# 94330_SKYPULSE_IOC_V1_2.net
KiCad netlist of a schematic drawn in Altium Designer
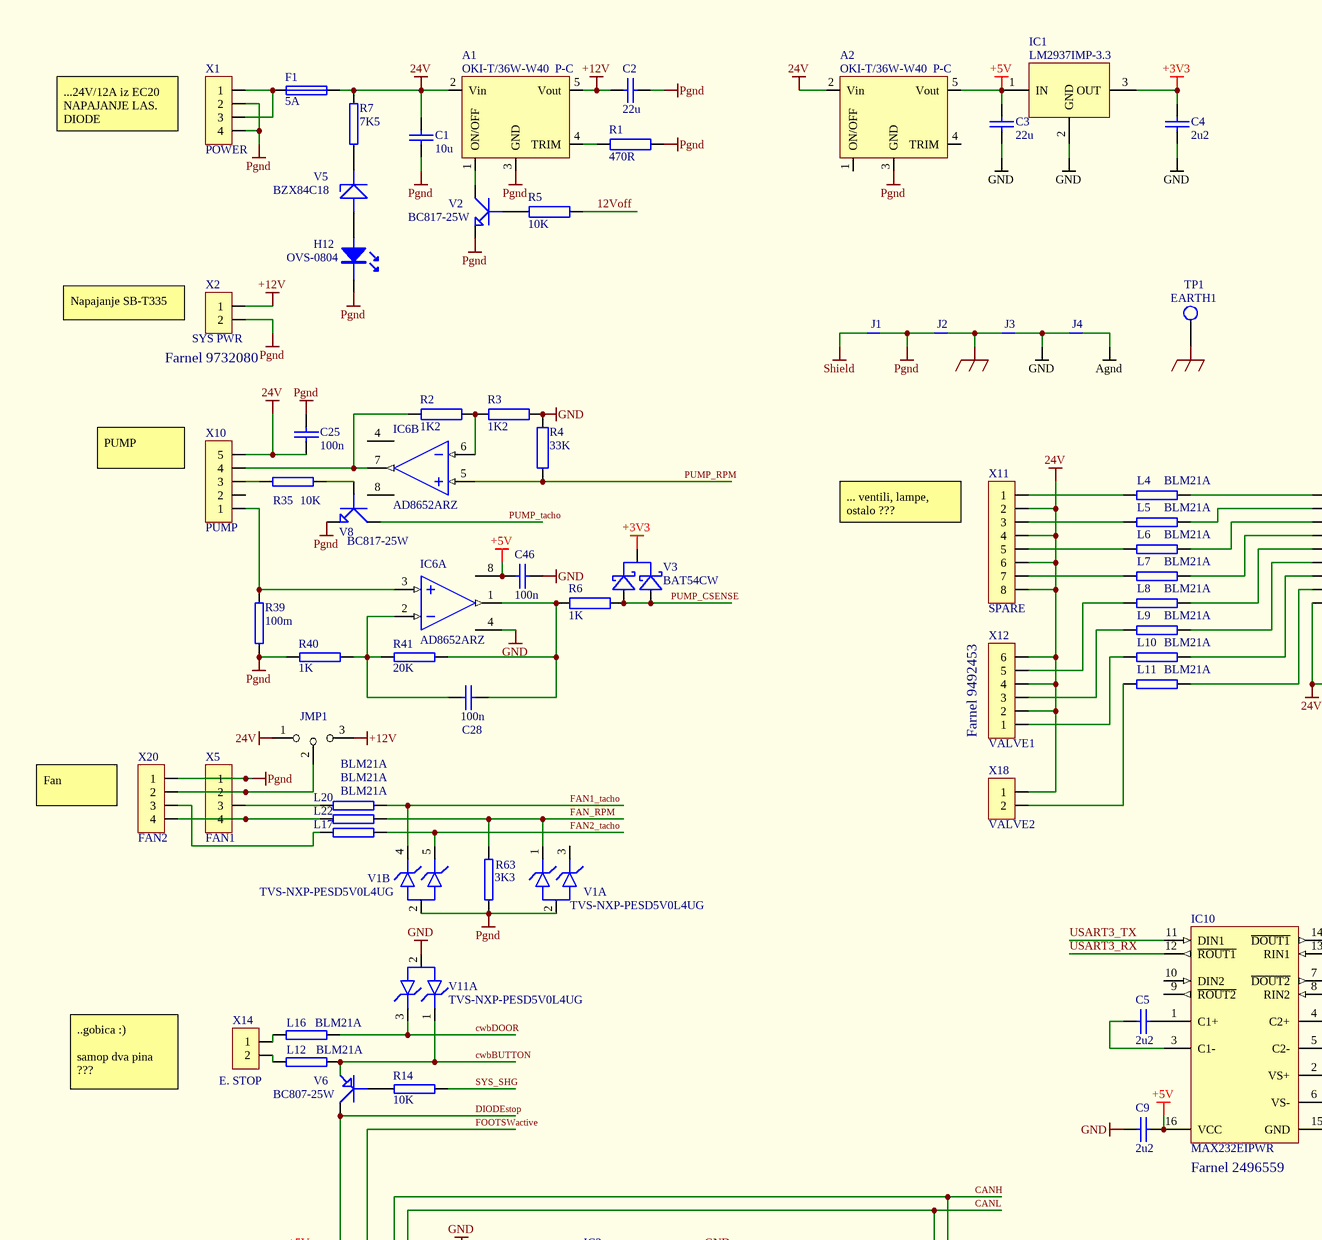
[diagram p0: 94330_SKYPULSE IOC_V1.2.SchDoc, top left]
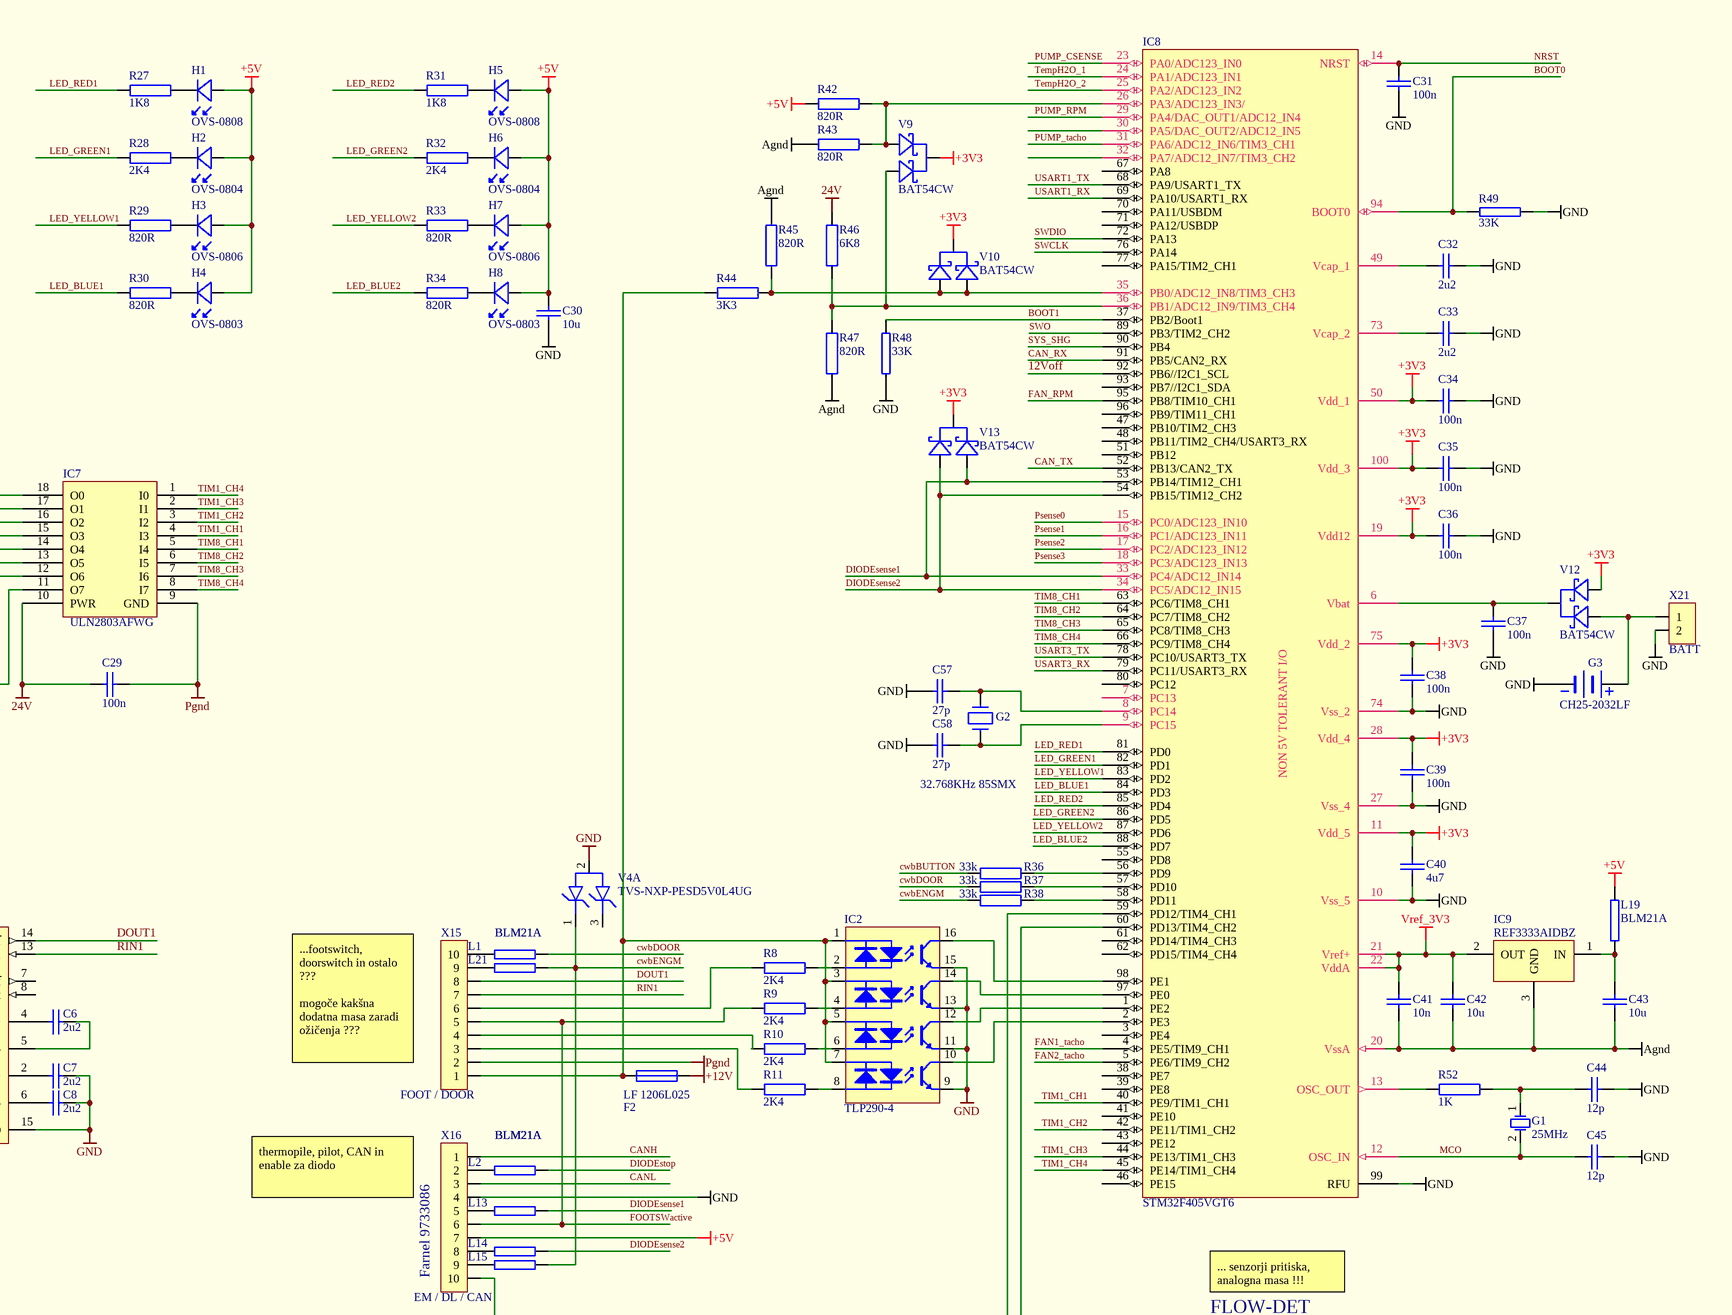
[diagram p1: 94330_SKYPULSE IOC_V1.2.SchDoc, top right]
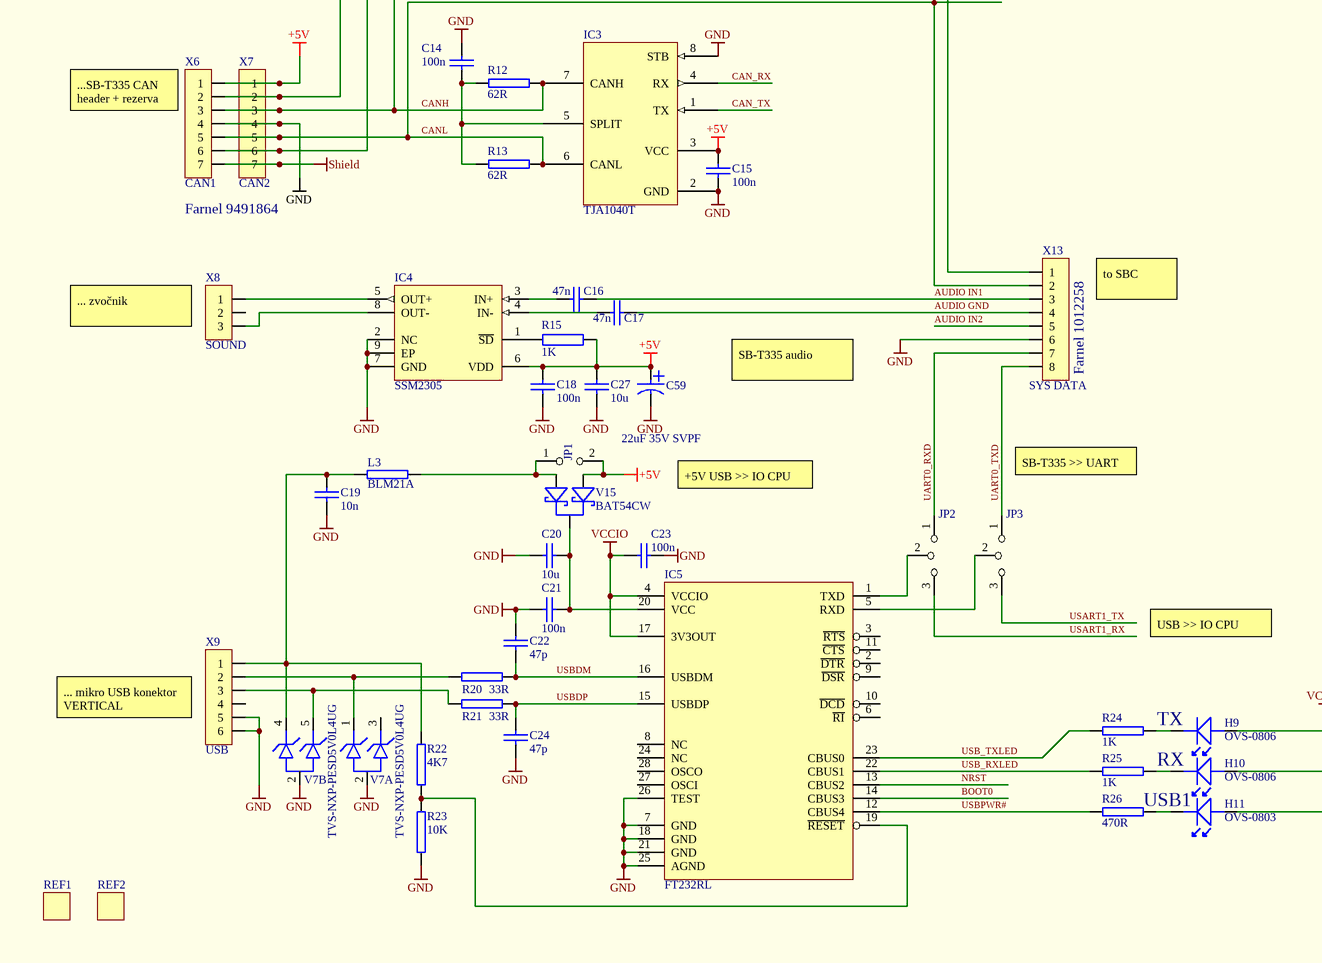
[diagram p2: 94330_SKYPULSE IOC_V1.2.SchDoc, bottom left]
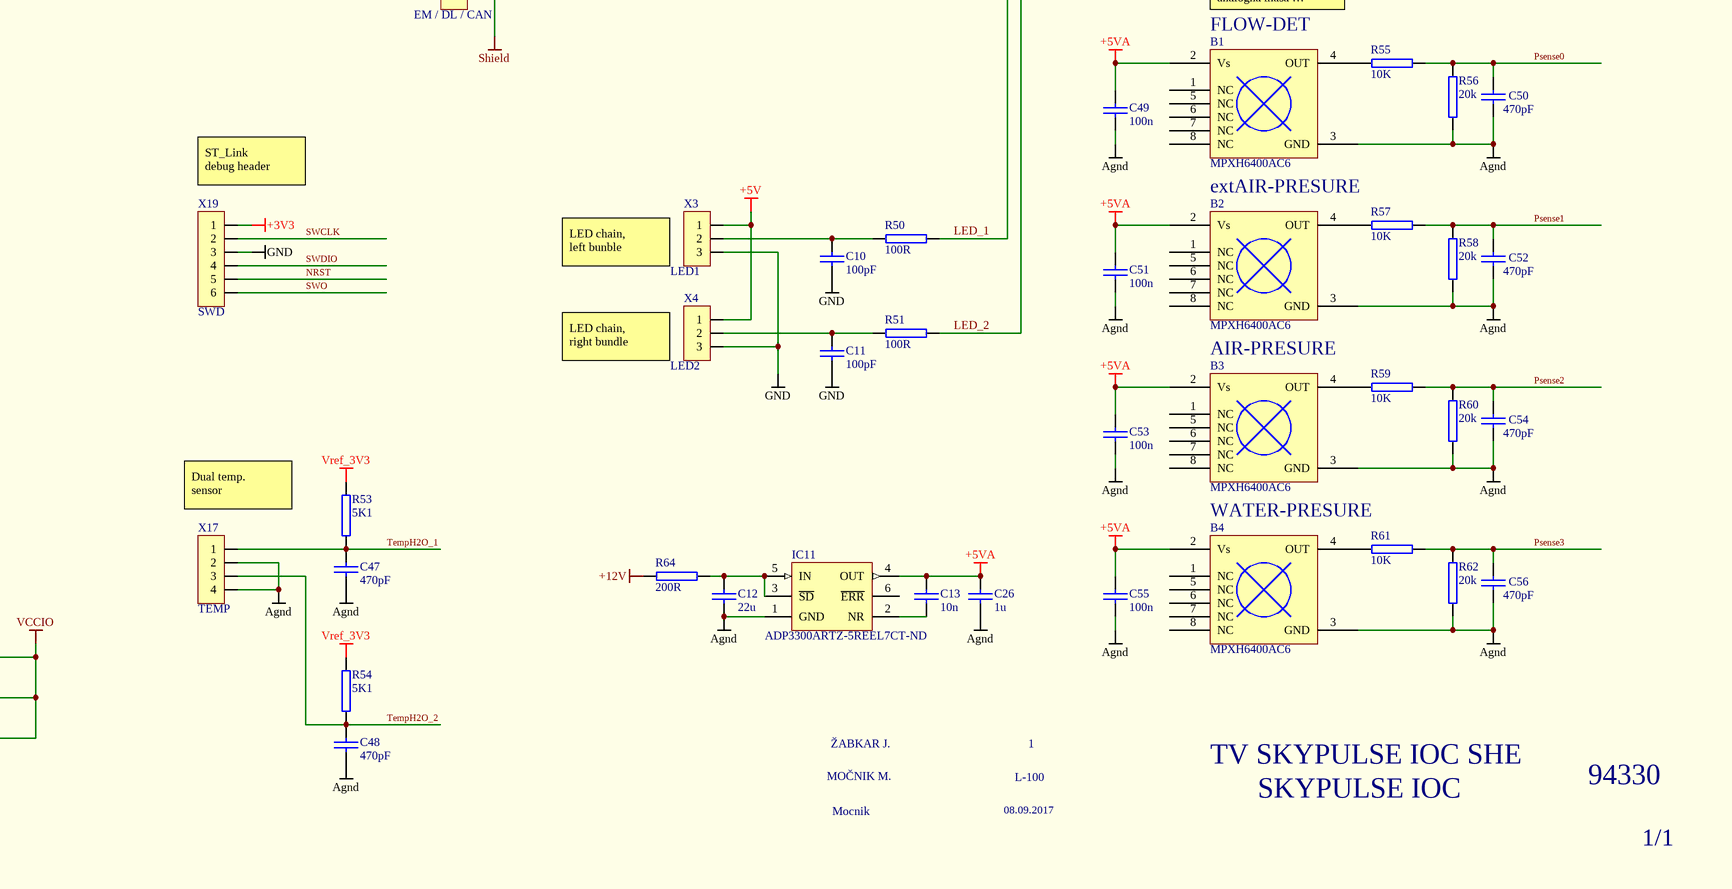
[diagram p3: 94330_SKYPULSE IOC_V1.2.SchDoc, bottom right]

(export (version "E")
  (design (tool "Eeschema 10.0.6"))
  (components
    (comp (ref "A1")
      (value "OKI-T/36W-W40  P-C")
      (footprint "DC-DC_OKI-T/36W-W40")
      (libsource (lib "Mlk-sch") (part "MURATA_OKI-T/36W-W40  X-C"))
    )
    (comp (ref "A2")
      (value "OKI-T/36W-W40  P-C")
      (footprint "DC-DC_OKI-T/36W-W40")
      (libsource (lib "Mlk-sch") (part "MURATA_OKI-T/36W-W40  X-C"))
    )
    (comp (ref "B1")
      (value "MPXH6400AC6")
      (footprint "SOIC127P1030-8N_MPXH6400AC6")
      (description "MPXH6400A Pressure sensor, 400kPa")
      (libsource (lib "*") (part "MPXH6400A"))
    )
    (comp (ref "B2")
      (value "MPXH6400AC6")
      (footprint "SOIC127P1030-8N_MPXH6400AC6")
      (description "MPXH6400A Pressure sensor, 400kPa")
      (libsource (lib "*") (part "MPXH6400A"))
    )
    (comp (ref "B3")
      (value "MPXH6400AC6")
      (footprint "SOIC127P1030-8N_MPXH6400AC6")
      (description "MPXH6400A Pressure sensor, 400kPa")
      (libsource (lib "*") (part "MPXH6400A"))
    )
    (comp (ref "B4")
      (value "MPXH6400AC6")
      (footprint "SOIC127P1030-8N_MPXH6400AC6")
      (description "MPXH6400A Pressure sensor, 400kPa")
      (libsource (lib "*") (part "MPXH6400A"))
    )
    (comp (ref "C1")
      (value "10u")
      (footprint "CAPC3225N")
      (description "Capacitor 1210")
      (libsource (lib "altium-import") (part "root_2_Cap_"))
    )
    (comp (ref "C2")
      (value "22u")
      (footprint "CAPC3225N")
      (description "Capacitor 1210")
      (libsource (lib "altium-import") (part "root_1_Cap_"))
    )
    (comp (ref "C3")
      (value "22u")
      (footprint "CAPC3225N")
      (description "Capacitor 1210")
      (libsource (lib "altium-import") (part "root_0_Cap_"))
    )
    (comp (ref "C4")
      (value "2u2")
      (footprint "0805-C-IPC-V")
      (description "Capacitor 0805")
      (libsource (lib "altium-import") (part "root_0_Cap_"))
    )
    (comp (ref "C5")
      (value "2u2")
      (footprint "0805-C-IPC-V")
      (description "Capacitor 0805")
      (libsource (lib "altium-import") (part "root_1_Cap_"))
    )
    (comp (ref "C6")
      (value "2u2")
      (footprint "0805-C-IPC-V")
      (description "Capacitor 0805")
      (libsource (lib "altium-import") (part "root_1_Cap_"))
    )
    (comp (ref "C7")
      (value "2u2")
      (footprint "0805-C-IPC-V")
      (description "Capacitor 0805")
      (libsource (lib "altium-import") (part "root_1_Cap_"))
    )
    (comp (ref "C8")
      (value "2u2")
      (footprint "0805-C-IPC-V")
      (description "Capacitor 0805")
      (libsource (lib "altium-import") (part "root_1_Cap_"))
    )
    (comp (ref "C9")
      (value "2u2")
      (footprint "0805-C-IPC-V")
      (description "Capacitor 0805")
      (libsource (lib "altium-import") (part "root_3_Cap_"))
    )
    (comp (ref "C10")
      (value "100pF")
      (footprint "0805-C-IPC-V")
      (description "Capacitor 0805")
      (libsource (lib "*") (part "C"))
    )
    (comp (ref "C11")
      (value "100pF")
      (footprint "0805-C-IPC-V")
      (description "Capacitor 0805")
      (libsource (lib "*") (part "C"))
    )
    (comp (ref "C12")
      (value "22u")
      (footprint "CAPC3225N")
      (description "Capacitor 1210")
      (libsource (lib "altium-import") (part "root_2_Cap_"))
    )
    (comp (ref "C13")
      (value "10n")
      (footprint "0805-C-IPC-V")
      (description "Capacitor 0805")
      (libsource (lib "Main") (part "C"))
    )
    (comp (ref "C14")
      (value "100n")
      (footprint "0805-C-IPC-V")
      (description "Capacitor 0805")
      (libsource (lib "Main") (part "C"))
    )
    (comp (ref "C15")
      (value "100n")
      (footprint "0805-C-IPC-V")
      (description "Capacitor 0805")
      (libsource (lib "Main") (part "C"))
    )
    (comp (ref "C16")
      (value "47n")
      (footprint "0805-C-IPC-V")
      (description "Capacitor 0805")
      (libsource (lib "Main") (part "C"))
    )
    (comp (ref "C17")
      (value "47n")
      (footprint "0805-C-IPC-V")
      (description "Capacitor 0805")
      (libsource (lib "Main") (part "C"))
    )
    (comp (ref "C18")
      (value "100n")
      (footprint "0805-C-IPC-V")
      (description "Capacitor 0805")
      (libsource (lib "Main") (part "C"))
    )
    (comp (ref "C19")
      (value "10n")
      (footprint "0805-C-IPC-V")
      (description "Capacitor 0805")
      (libsource (lib "*") (part "C"))
    )
    (comp (ref "C20")
      (value "10u")
      (footprint "0805-C-IPC-V")
      (description "Capacitor 0805")
      (libsource (lib "*") (part "CAP"))
    )
    (comp (ref "C21")
      (value "100n")
      (footprint "0805-C-IPC-V")
      (description "Capacitor 0805")
      (libsource (lib "*") (part "C"))
    )
    (comp (ref "C22")
      (value "47p")
      (footprint "0805-C-V")
      (description "Capacitor 0805")
      (libsource (lib "*") (part "C"))
    )
    (comp (ref "C23")
      (value "100n")
      (footprint "0805-C-IPC-V")
      (description "Capacitor 0805")
      (libsource (lib "*") (part "C"))
    )
    (comp (ref "C24")
      (value "47p")
      (footprint "0805-C-V")
      (description "Capacitor 0805")
      (libsource (lib "*") (part "C"))
    )
    (comp (ref "C25")
      (value "100n")
      (footprint "0805-C-IPC-V")
      (description "Capacitor 0805")
      (libsource (lib "*") (part "C"))
    )
    (comp (ref "C26")
      (value "1u")
      (footprint "0805-C-IPC-V")
      (description "Capacitor 0805")
      (libsource (lib "Main") (part "C"))
    )
    (comp (ref "C27")
      (value "10u")
      (footprint "0805-C-IPC-V")
      (description "Capacitor 0805")
      (libsource (lib "altium-import") (part "root_2_Cap_"))
    )
    (comp (ref "C28")
      (value "100n")
      (footprint "0805-C-IPC-V")
      (description "Capacitor 0805")
      (libsource (lib "Fotona") (part "Cap"))
    )
    (comp (ref "C29")
      (value "100n")
      (footprint "0805-C-IPC-V")
      (description "Capacitor 0805")
      (libsource (lib "Main") (part "C"))
    )
    (comp (ref "C30")
      (value "10u")
      (footprint "0805-C-IPC-V")
      (description "Capacitor 0805")
      (libsource (lib "Fotona") (part "Cap"))
    )
    (comp (ref "C31")
      (value "100n")
      (footprint "0805-C-IPC-V")
      (description "Capacitor 0805")
      (libsource (lib "Fotona") (part "Cap"))
    )
    (comp (ref "C32")
      (value "2u2")
      (footprint "0805-C-IPC-V")
      (description "Capacitor 0805")
      (libsource (lib "Fotona") (part "Cap"))
    )
    (comp (ref "C33")
      (value "2u2")
      (footprint "0805-C-IPC-V")
      (description "Capacitor 0805")
      (libsource (lib "Fotona") (part "Cap"))
    )
    (comp (ref "C34")
      (value "100n")
      (footprint "0805-C-IPC-V")
      (description "Capacitor 0805")
      (libsource (lib "Main") (part "C"))
    )
    (comp (ref "C35")
      (value "100n")
      (footprint "0805-C-IPC-V")
      (description "Capacitor 0805")
      (libsource (lib "Main") (part "C"))
    )
    (comp (ref "C36")
      (value "100n")
      (footprint "0805-C-IPC-V")
      (description "Capacitor 0805")
      (libsource (lib "Main") (part "C"))
    )
    (comp (ref "C37")
      (value "100n")
      (footprint "0805-C-IPC-V")
      (description "Capacitor 0805")
      (libsource (lib "Main") (part "C"))
    )
    (comp (ref "C38")
      (value "100n")
      (footprint "0805-C-IPC-V")
      (description "Capacitor 0805")
      (libsource (lib "Main") (part "C"))
    )
    (comp (ref "C39")
      (value "100n")
      (footprint "0805-C-IPC-V")
      (description "Capacitor 0805")
      (libsource (lib "Main") (part "C"))
    )
    (comp (ref "C40")
      (value "4u7")
      (footprint "0805-C-IPC-V")
      (description "Capacitor 0805")
      (libsource (lib "Fotona") (part "Cap"))
    )
    (comp (ref "C41")
      (value "10n")
      (footprint "0805-C-IPC-V")
      (description "Capacitor 0805")
      (libsource (lib "Fotona") (part "Cap"))
    )
    (comp (ref "C42")
      (value "10u")
      (footprint "0805-C-IPC-V")
      (description "Capacitor 0805")
      (libsource (lib "Fotona") (part "Cap"))
    )
    (comp (ref "C43")
      (value "10u")
      (footprint "0805-C-IPC-V")
      (description "Capacitor 0805")
      (libsource (lib "Fotona") (part "Cap"))
    )
    (comp (ref "C44")
      (value "12p")
      (footprint "0805-C-IPC-V")
      (description "Capacitor 0603")
      (libsource (lib "Fotona") (part "Cap"))
    )
    (comp (ref "C45")
      (value "12p")
      (footprint "0805-C-IPC-V")
      (description "Capacitor 0603")
      (libsource (lib "Fotona") (part "Cap"))
    )
    (comp (ref "C46")
      (value "100n")
      (footprint "0805-C-IPC-V")
      (description "Capacitor 0805")
      (libsource (lib "Fotona") (part "Cap"))
    )
    (comp (ref "C47")
      (value "470pF")
      (footprint "0805-C-IPC-V")
      (description "Capacitor 0805")
      (libsource (lib "*") (part "C"))
    )
    (comp (ref "C48")
      (value "470pF")
      (footprint "0805-C-IPC-V")
      (description "Capacitor 0805")
      (libsource (lib "*") (part "C"))
    )
    (comp (ref "C49")
      (value "100n")
      (footprint "0805-C-IPC-V")
      (description "Capacitor 0805")
      (libsource (lib "Main") (part "C"))
    )
    (comp (ref "C50")
      (value "470pF")
      (footprint "0805-C-IPC-V")
      (description "Capacitor 0805")
      (libsource (lib "*") (part "C"))
    )
    (comp (ref "C51")
      (value "100n")
      (footprint "0805-C-IPC-V")
      (description "Capacitor 0805")
      (libsource (lib "Main") (part "C"))
    )
    (comp (ref "C52")
      (value "470pF")
      (footprint "0805-C-IPC-V")
      (description "Capacitor 0805")
      (libsource (lib "*") (part "C"))
    )
    (comp (ref "C53")
      (value "100n")
      (footprint "0805-C-IPC-V")
      (description "Capacitor 0805")
      (libsource (lib "Main") (part "C"))
    )
    (comp (ref "C54")
      (value "470pF")
      (footprint "0805-C-IPC-V")
      (description "Capacitor 0805")
      (libsource (lib "*") (part "C"))
    )
    (comp (ref "C55")
      (value "100n")
      (footprint "0805-C-IPC-V")
      (description "Capacitor 0805")
      (libsource (lib "Main") (part "C"))
    )
    (comp (ref "C56")
      (value "470pF")
      (footprint "0805-C-IPC-V")
      (description "Capacitor 0805")
      (libsource (lib "*") (part "C"))
    )
    (comp (ref "C57")
      (value "27p")
      (footprint "0805-C-IPC-V")
      (description "Capacitor 0603")
      (libsource (lib "Fotona") (part "Cap"))
    )
    (comp (ref "C58")
      (value "27p")
      (footprint "0805-C-IPC-V")
      (description "Capacitor 0603")
      (libsource (lib "Fotona") (part "Cap"))
    )
    (comp (ref "C59")
      (value "22uF 35V SVPF")
      (footprint "CAPAE66W54HN")
      (libsource (lib "Mlk-sch") (part "C-EL"))
    )
    (comp (ref "F1")
      (value "5A")
      (footprint "FUSE_154_ LITTELFUSE")
      (description "FUSE")
      (libsource (lib "MA_DEVICE_1") (part "FUSE"))
    )
    (comp (ref "F2") (value "LF 1206L025") (footprint "FUSEC3216X09N") (libsource (lib "*") (part "FUSE1")))
    (comp (ref "G1")
      (value "25MHz")
      (footprint "JXG53P2")
      (description "SMD Quartz Crystal")
      (libsource (lib "Fotona") (part "XTAL"))
    )
    (comp (ref "G2")
      (value "32.768KHz 85SMX")
      (footprint "QUARTZ-85SMX")
      (libsource (lib "*") (part "CRYSTAL"))
    )
    (comp (ref "G3")
      (value "CH25-2032LF")
      (footprint "BATTERY HOLDER-20")
      (description "Li CELL 3V, 3/2 PIN, HOR/VERT POS")
      (libsource (lib "Mlk-sch") (part "BATTERY LI 3V"))
    )
    (comp (ref "H1")
      (value "OVS-0808")
      (footprint "LED_0805_RED")
      (description "LED")
      (libsource (lib "Fotona") (part "LED"))
    )
    (comp (ref "H2")
      (value "OVS-0804")
      (footprint "LED_0805_GREEN")
      (description "LED")
      (libsource (lib "Fotona") (part "LED"))
    )
    (comp (ref "H3")
      (value "OVS-0806")
      (footprint "LED_0805_YELLOW")
      (description "LED")
      (libsource (lib "Fotona") (part "LED"))
    )
    (comp (ref "H4")
      (value "OVS-0803")
      (footprint "LED_0805_BLUE")
      (description "LED")
      (libsource (lib "Fotona") (part "LED"))
    )
    (comp (ref "H5")
      (value "OVS-0808")
      (footprint "LED_0805_RED")
      (description "LED")
      (libsource (lib "Fotona") (part "LED"))
    )
    (comp (ref "H6")
      (value "OVS-0804")
      (footprint "LED_0805_GREEN")
      (description "LED")
      (libsource (lib "Fotona") (part "LED"))
    )
    (comp (ref "H7")
      (value "OVS-0806")
      (footprint "LED_0805_YELLOW")
      (description "LED")
      (libsource (lib "Fotona") (part "LED"))
    )
    (comp (ref "H8")
      (value "OVS-0803")
      (footprint "LED_0805_BLUE")
      (description "LED")
      (libsource (lib "Fotona") (part "LED"))
    )
    (comp (ref "H9")
      (value "OVS-0806")
      (footprint "LED_0805_YELLOW")
      (description "LED")
      (libsource (lib "*") (part "LED0805"))
    )
    (comp (ref "H10")
      (value "OVS-0806")
      (footprint "LED_0805_YELLOW")
      (description "LED")
      (libsource (lib "*") (part "LED0805"))
    )
    (comp (ref "H11")
      (value "OVS-0803")
      (footprint "LED_0805_BLUE")
      (description "LED")
      (libsource (lib "*") (part "LED0805"))
    )
    (comp (ref "H12")
      (value "OVS-0804")
      (footprint "LED_0805_GREEN")
      (description "LED")
      (libsource (lib "MA_DEVICE_1") (part "D_LED"))
    )
    (comp (ref "IC1")
      (value "LM2937IMP-3.3")
      (footprint "FOTONA_IPC7351_DISCRETE:SOT223-4N-V")
      (description "Fixed 3V3 Regulator")
      (libsource (lib "Fotona") (part "LM2937IMP"))
    )
    (comp (ref "IC2")
      (value "TLP290-4")
      (footprint "SOIC127P700X265-16N")
      (libsource (lib "Mlk-sch") (part "OPTOCOUPLER-QUAD"))
    )
    (comp (ref "IC3") (value "TJA1040T") (footprint "SO_8") (libsource (lib "*") (part "TJA1040")))
    (comp (ref "IC4")
      (value "SSM2305")
      (footprint "SON50P300X85_HS-9N")
      (libsource (lib "Mlk-sch") (part "SSM2305"))
    )
    (comp (ref "IC5")
      (value "FT232RL")
      (footprint "SOP65P780-28N")
      (description "USB to Serial port converter")
      (libsource (lib "*") (part "FT232RL"))
    )
    (comp (ref "IC6")
      (value "AD8652ARZ")
      (footprint "SOIC127P600-8N")
      (description "Dual CMOS RR Op Amp")
      (libsource (lib "Fotona") (part "OPAMP_DUAL"))
    )
    (comp (ref "IC7")
      (value "ULN2803AFWG")
      (footprint "SOIC127P1030-18N")
      (description "COIL DRIVER")
      (libsource (lib "*") (part "ULN2804"))
    )
    (comp (ref "IC8")
      (value "STM32F405VGT6")
      (footprint "LQFP100_N")
      (description "STM32 ARM-based 32-bit MCU with 1024 Kbytes Flash, 100-pin LQFP")
      (libsource (lib "Fotona") (part "STM32F205VGT6"))
    )
    (comp (ref "IC9")
      (value "REF3333AIDBZ")
      (footprint "FOTONA_IPC7351_DISCRETE:SOT23-3N")
      (description "3V3 Voltage Reference")
      (libsource (lib "Fotona") (part "REF33XX"))
    )
    (comp (ref "IC10")
      (value "MAX232EIPWR")
      (footprint "FOTONA_IPC7351_SO:TSOP65P640-16N")
      (libsource (lib "altium-import") (part "root_0_CMP-0299-00572-2_"))
    )
    (comp (ref "IC11")
      (value "ADP3300ARTZ-5REEL7CT-ND")
      (footprint "SOT23-6N")
      (libsource (lib "Mlk-sch") (part "ADP3300"))
    )
    (comp (ref "J1") (value "JMP-GND") (footprint "JMP-GND") (libsource (lib "Mlk-sch") (part "JMP-GND")))
    (comp (ref "J2") (value "JMP-GND") (footprint "JMP-GND") (libsource (lib "Mlk-sch") (part "JMP-GND")))
    (comp (ref "J3") (value "JMP-GND") (footprint "JMP-GND") (libsource (lib "Mlk-sch") (part "JMP-GND")))
    (comp (ref "J4") (value "JMP-GND") (footprint "JMP-GND") (libsource (lib "Mlk-sch") (part "JMP-GND")))
    (comp (ref "JMP1") (value "~") (description "JUMPER") (libsource (lib "MA_DEVICE_1") (part "JMP3")))
    (comp (ref "JP1")
      (value "JMP2")
      (footprint "SIP_2")
      (description "JUMPER")
      (libsource (lib "MA_DEVICE_1") (part "JMP2"))
    )
    (comp (ref "JP2")
      (value "~")
      (footprint "SIP_3")
      (description "JUMPER")
      (libsource (lib "MA_DEVICE_1") (part "JMP3"))
    )
    (comp (ref "JP3")
      (value "~")
      (footprint "SIP_3")
      (description "JUMPER")
      (libsource (lib "MA_DEVICE_1") (part "JMP3"))
    )
    (comp (ref "L1")
      (value "BLM21A")
      (footprint "INDC2012N")
      (description "Ferite Bead SMT")
      (libsource (lib "*") (part "BLM21"))
    )
    (comp (ref "L2")
      (value "BLM21A")
      (footprint "INDC2012N")
      (description "Ferite Bead SMT")
      (libsource (lib "*") (part "BLM21"))
    )
    (comp (ref "L3")
      (value "BLM21A")
      (footprint "INDC2012N")
      (description "Ferite Bead SMT")
      (libsource (lib "*") (part "BLM21"))
    )
    (comp (ref "L4")
      (value "BLM21A")
      (footprint "INDC2012N")
      (description "FERITE MURATA BLM21")
      (libsource (lib "*") (part "BLM21"))
    )
    (comp (ref "L5")
      (value "BLM21A")
      (footprint "INDC2012N")
      (description "FERITE MURATA BLM21")
      (libsource (lib "*") (part "BLM21"))
    )
    (comp (ref "L6")
      (value "BLM21A")
      (footprint "INDC2012N")
      (description "FERITE MURATA BLM21")
      (libsource (lib "*") (part "BLM21"))
    )
    (comp (ref "L7")
      (value "BLM21A")
      (footprint "INDC2012N")
      (description "FERITE MURATA BLM21")
      (libsource (lib "*") (part "BLM21"))
    )
    (comp (ref "L8")
      (value "BLM21A")
      (footprint "INDC2012N")
      (description "FERITE MURATA BLM21")
      (libsource (lib "*") (part "BLM21"))
    )
    (comp (ref "L9")
      (value "BLM21A")
      (footprint "INDC2012N")
      (description "FERITE MURATA BLM21")
      (libsource (lib "*") (part "BLM21"))
    )
    (comp (ref "L10")
      (value "BLM21A")
      (footprint "INDC2012N")
      (description "FERITE MURATA BLM21")
      (libsource (lib "*") (part "BLM21"))
    )
    (comp (ref "L11")
      (value "BLM21A")
      (footprint "INDC2012N")
      (description "FERITE MURATA BLM21")
      (libsource (lib "*") (part "BLM21"))
    )
    (comp (ref "L12")
      (value "BLM21A")
      (footprint "INDC2012N")
      (description "Ferite Bead SMT")
      (libsource (lib "*") (part "BLM21"))
    )
    (comp (ref "L13")
      (value "BLM21A")
      (footprint "INDC2012N")
      (description "Ferite Bead SMT")
      (libsource (lib "*") (part "BLM21"))
    )
    (comp (ref "L14")
      (value "BLM21A")
      (footprint "INDC2012N")
      (description "Ferite Bead SMT")
      (libsource (lib "*") (part "BLM21"))
    )
    (comp (ref "L15")
      (value "BLM21A")
      (footprint "INDC2012N")
      (description "Ferite Bead SMT")
      (libsource (lib "*") (part "BLM21"))
    )
    (comp (ref "L16")
      (value "BLM21A")
      (footprint "INDC2012N")
      (description "Ferite Bead SMT")
      (libsource (lib "*") (part "BLM21"))
    )
    (comp (ref "L17")
      (value "BLM21A")
      (footprint "INDC2012N")
      (description "FERITE MURATA BLM21")
      (libsource (lib "*") (part "BLM21"))
    )
    (comp (ref "L19")
      (value "BLM21A")
      (footprint "INDC2012N")
      (description "Ferite Bead SMT")
      (libsource (lib "*") (part "BLM21"))
    )
    (comp (ref "L20")
      (value "BLM21A")
      (footprint "INDC2012N")
      (description "FERITE MURATA BLM21")
      (libsource (lib "*") (part "BLM21"))
    )
    (comp (ref "L21")
      (value "BLM21A")
      (footprint "INDC2012N")
      (description "Ferite Bead SMT")
      (libsource (lib "*") (part "BLM21"))
    )
    (comp (ref "L22")
      (value "BLM21A")
      (footprint "INDC2012N")
      (description "FERITE MURATA BLM21")
      (libsource (lib "*") (part "BLM21"))
    )
    (comp (ref "R1")
      (value "470R")
      (footprint "0805-R-IPC-V")
      (description "Chip Resistor 0805")
      (libsource (lib "Fotona") (part "Res"))
    )
    (comp (ref "R2")
      (value "1K2")
      (footprint "0805-R-IPC-V")
      (description "Chip Resistor 0805")
      (libsource (lib "Fotona") (part "Res"))
    )
    (comp (ref "R3")
      (value "1K2")
      (footprint "0805-R-IPC-V")
      (description "Chip Resistor 0805")
      (libsource (lib "Fotona") (part "Res"))
    )
    (comp (ref "R4")
      (value "33K")
      (footprint "0805-R-V")
      (description "Chip Resistor 0805")
      (libsource (lib "Fotona") (part "Res"))
    )
    (comp (ref "R5")
      (value "10K")
      (footprint "0805-R-IPC-V")
      (description "Chip Resistor 0805")
      (libsource (lib "Fotona") (part "Res"))
    )
    (comp (ref "R6")
      (value "1K")
      (footprint "0805-R-IPC-V")
      (description "Chip Resistor 0805")
      (libsource (lib "Fotona") (part "Res"))
    )
    (comp (ref "R7")
      (value "7K5")
      (footprint "0805-R-IPC-V")
      (description "Resistor")
      (libsource (lib "*") (part "R"))
    )
    (comp (ref "R8")
      (value "2K4")
      (footprint "0805-R-IPC-V")
      (description "Chip Resistor 0805")
      (libsource (lib "Fotona") (part "Res"))
    )
    (comp (ref "R9")
      (value "2K4")
      (footprint "0805-R-IPC-V")
      (description "Chip Resistor 0805")
      (libsource (lib "Fotona") (part "Res"))
    )
    (comp (ref "R10")
      (value "2K4")
      (footprint "0805-R-IPC-V")
      (description "Chip Resistor 0805")
      (libsource (lib "Fotona") (part "Res"))
    )
    (comp (ref "R11")
      (value "2K4")
      (footprint "0805-R-IPC-V")
      (description "Chip Resistor 0805")
      (libsource (lib "Fotona") (part "Res"))
    )
    (comp (ref "R12")
      (value "62R")
      (footprint "0805-R-IPC-V")
      (description "Resistor")
      (libsource (lib "Main") (part "R"))
    )
    (comp (ref "R13")
      (value "62R")
      (footprint "0805-R-IPC-V")
      (description "Resistor")
      (libsource (lib "Main") (part "R"))
    )
    (comp (ref "R14")
      (value "10K")
      (footprint "0805-R-IPC-V")
      (description "Resistor")
      (libsource (lib "Main") (part "R"))
    )
    (comp (ref "R15")
      (value "1K")
      (footprint "0805-R-IPC-V")
      (description "Chip Resistor 0805")
      (libsource (lib "Fotona") (part "Res"))
    )
    (comp (ref "R20")
      (value "33R")
      (footprint "0805-R-IPC-V")
      (description "Resistor")
      (libsource (lib "*") (part "R"))
    )
    (comp (ref "R21")
      (value "33R")
      (footprint "0805-R-IPC-V")
      (description "Resistor")
      (libsource (lib "*") (part "R"))
    )
    (comp (ref "R22")
      (value "4K7")
      (footprint "0805-R-IPC-V")
      (description "Resistor")
      (libsource (lib "*") (part "R"))
    )
    (comp (ref "R23")
      (value "10K")
      (footprint "0805-R-IPC-V")
      (description "Resistor")
      (libsource (lib "*") (part "R"))
    )
    (comp (ref "R24")
      (value "1K")
      (footprint "0805-R-IPC-V")
      (description "Resistor")
      (libsource (lib "*") (part "R"))
    )
    (comp (ref "R25")
      (value "1K")
      (footprint "0805-R-IPC-V")
      (description "Resistor")
      (libsource (lib "*") (part "R"))
    )
    (comp (ref "R26")
      (value "470R")
      (footprint "0805-R-IPC-V")
      (description "Resistor")
      (libsource (lib "*") (part "R"))
    )
    (comp (ref "R27")
      (value "1K8")
      (footprint "0805-R-IPC-V")
      (description "Chip Resistor 0805")
      (libsource (lib "Fotona") (part "Res"))
    )
    (comp (ref "R28")
      (value "2K4")
      (footprint "0805-R-IPC-V")
      (description "Chip Resistor 0805")
      (libsource (lib "Fotona") (part "Res"))
    )
    (comp (ref "R29")
      (value "820R")
      (footprint "0805-R-IPC-V")
      (description "Chip Resistor 0805")
      (libsource (lib "Fotona") (part "Res"))
    )
    (comp (ref "R30")
      (value "820R")
      (footprint "0805-R-IPC-V")
      (description "Chip Resistor 0805")
      (libsource (lib "Fotona") (part "Res"))
    )
    (comp (ref "R31")
      (value "1K8")
      (footprint "0805-R-IPC-V")
      (description "Chip Resistor 0805")
      (libsource (lib "Fotona") (part "Res"))
    )
    (comp (ref "R32")
      (value "2K4")
      (footprint "0805-R-IPC-V")
      (description "Chip Resistor 0805")
      (libsource (lib "Fotona") (part "Res"))
    )
    (comp (ref "R33")
      (value "820R")
      (footprint "0805-R-IPC-V")
      (description "Chip Resistor 0805")
      (libsource (lib "Fotona") (part "Res"))
    )
    (comp (ref "R34")
      (value "820R")
      (footprint "0805-R-IPC-V")
      (description "Chip Resistor 0805")
      (libsource (lib "Fotona") (part "Res"))
    )
    (comp (ref "R35")
      (value "10K")
      (footprint "0805-R-IPC-V")
      (description "Resistor")
      (libsource (lib "Main") (part "R"))
    )
    (comp (ref "R36")
      (value "33k")
      (footprint "0805-R-IPC-V")
      (description "Chip Resistor 0402")
      (fields (field (name "TOLERANCE") "1%") (field (name "POWER") "0.063W"))
      (libsource (lib "Fotona") (part "Res"))
    )
    (comp (ref "R37")
      (value "33k")
      (footprint "0805-R-IPC-V")
      (description "Chip Resistor 0402")
      (fields (field (name "TOLERANCE") "1%") (field (name "POWER") "0.063W"))
      (libsource (lib "Fotona") (part "Res"))
    )
    (comp (ref "R38")
      (value "33k")
      (footprint "0805-R-IPC-V")
      (description "Chip Resistor 0402")
      (fields (field (name "TOLERANCE") "1%") (field (name "POWER") "0.063W"))
      (libsource (lib "Fotona") (part "Res"))
    )
    (comp (ref "R39")
      (value "100m")
      (footprint "RESC3216N")
      (description "Resistor")
      (libsource (lib "Main") (part "R"))
    )
    (comp (ref "R40")
      (value "1K")
      (footprint "0805-R-IPC-V")
      (description "Resistor")
      (libsource (lib "Main") (part "R"))
    )
    (comp (ref "R41")
      (value "20K")
      (footprint "0805-R-IPC-V")
      (description "Resistor")
      (libsource (lib "Main") (part "R"))
    )
    (comp (ref "R42")
      (value "820R")
      (footprint "0805-R-IPC-V")
      (description "Chip Resistor 0805")
      (libsource (lib "Fotona") (part "Res"))
    )
    (comp (ref "R43")
      (value "820R")
      (footprint "0805-R-IPC-V")
      (description "Chip Resistor 0805")
      (libsource (lib "Fotona") (part "Res"))
    )
    (comp (ref "R44")
      (value "3K3")
      (footprint "0805-R-IPC-V")
      (description "Chip Resistor 0805")
      (libsource (lib "Fotona") (part "Res"))
    )
    (comp (ref "R45")
      (value "820R")
      (footprint "0805-R-IPC-V")
      (description "Chip Resistor 0805")
      (libsource (lib "Fotona") (part "Res"))
    )
    (comp (ref "R46")
      (value "6K8")
      (footprint "0805-R-IPC-V")
      (description "Chip Resistor 0805")
      (libsource (lib "Fotona") (part "Res"))
    )
    (comp (ref "R47")
      (value "820R")
      (footprint "0805-R-IPC-V")
      (description "Chip Resistor 0805")
      (libsource (lib "Fotona") (part "Res"))
    )
    (comp (ref "R48")
      (value "33K")
      (footprint "0805-R-IPC-V")
      (description "Resistor")
      (libsource (lib "Main") (part "R"))
    )
    (comp (ref "R49")
      (value "33K")
      (footprint "0805-R-IPC-V")
      (description "Resistor")
      (libsource (lib "Main") (part "R"))
    )
    (comp (ref "R50")
      (value "100R")
      (footprint "0805-R-IPC-V")
      (description "Resistor")
      (libsource (lib "Main") (part "R"))
    )
    (comp (ref "R51")
      (value "100R")
      (footprint "0805-R-IPC-V")
      (description "Resistor")
      (libsource (lib "Main") (part "R"))
    )
    (comp (ref "R52")
      (value "1K")
      (footprint "0805-R-IPC-V")
      (description "Resistor")
      (libsource (lib "Fotona") (part "Res"))
    )
    (comp (ref "R53")
      (value "5K1")
      (footprint "0805-R-IPC-V")
      (description "Resistor")
      (libsource (lib "Main") (part "R"))
    )
    (comp (ref "R54")
      (value "5K1")
      (footprint "0805-R-IPC-V")
      (description "Resistor")
      (libsource (lib "Main") (part "R"))
    )
    (comp (ref "R55")
      (value "10K")
      (footprint "0805-R-IPC-V")
      (description "Resistor")
      (libsource (lib "Main") (part "R"))
    )
    (comp (ref "R56")
      (value "20k")
      (footprint "0805-R-IPC-V")
      (description "Resistor 0805")
      (libsource (lib "Main") (part "R"))
    )
    (comp (ref "R57")
      (value "10K")
      (footprint "0805-R-IPC-V")
      (description "Resistor")
      (libsource (lib "Main") (part "R"))
    )
    (comp (ref "R58")
      (value "20k")
      (footprint "0805-R-IPC-V")
      (description "Resistor 0805")
      (libsource (lib "Main") (part "R"))
    )
    (comp (ref "R59")
      (value "10K")
      (footprint "0805-R-IPC-V")
      (description "Resistor")
      (libsource (lib "Main") (part "R"))
    )
    (comp (ref "R60")
      (value "20k")
      (footprint "0805-R-IPC-V")
      (description "Resistor 0805")
      (libsource (lib "Main") (part "R"))
    )
    (comp (ref "R61")
      (value "10K")
      (footprint "0805-R-IPC-V")
      (description "Resistor")
      (libsource (lib "Main") (part "R"))
    )
    (comp (ref "R62")
      (value "20k")
      (footprint "0805-R-IPC-V")
      (description "Resistor 0805")
      (libsource (lib "Main") (part "R"))
    )
    (comp (ref "R63")
      (value "3K3")
      (footprint "0805-R-IPC-V")
      (description "Resistor")
      (libsource (lib "Main") (part "R"))
    )
    (comp (ref "R64")
      (value "200R")
      (footprint "RESC3216N")
      (description "Resistor")
      (libsource (lib "Main") (part "R"))
    )
    (comp (ref "REF1")
      (value "MEHAN_PART_1")
      (footprint "TP_REF")
      (libsource (lib "Altium_Device_AM_1") (part "MEHAN_PART_1"))
    )
    (comp (ref "REF2")
      (value "~")
      (footprint "TP_REF")
      (libsource (lib "Altium_Device_AM_1") (part "MEHAN_PART_1"))
    )
    (comp (ref "TP1") (value "EARTH1") (footprint "PAD") (libsource (lib "*") (part "TP")))
    (comp (ref "V1")
      (value "TVS-NXP-PESD5V0L4UG")
      (footprint "SC70-5")
      (description "TVS, NXP, PESD3V3L4UG, SOT665")
      (libsource (lib "*") (part "TVS-NXP-PESD3V3L4UG"))
    )
    (comp (ref "V2")
      (value "BC817-25W")
      (footprint "SOT323-3N-CBE")
      (description "NPN Bipolar Transistor")
      (libsource (lib "Fotona") (part "TRANSISTOR_NPN"))
    )
    (comp (ref "V3")
      (value "BAT54CW")
      (footprint "FOTONA_IPC7351_DISCRETE:SOT323-3N")
      (description "Diode Schottky Common Chatode")
      (libsource (lib "Fotona") (part "D_SCH_CK_1A1-2A2-3K"))
    )
    (comp (ref "V4")
      (value "TVS-NXP-PESD5V0L4UG")
      (footprint "SC70-5")
      (description "TVS, NXP, PESD3V3L4UG, SOT665")
      (libsource (lib "*") (part "TVS-NXP-PESD3V3L4UG"))
    )
    (comp (ref "V5")
      (value "BZX84C18")
      (footprint "SOT_23/D1")
      (description "Zener Diode")
      (libsource (lib "*") (part "ZD"))
    )
    (comp (ref "V6")
      (value "BC807-25W")
      (footprint "SOT323-3N-CBE")
      (description "PNP Bipolar Transistor")
      (libsource (lib "Fotona") (part "TRANSISTOR_PNP_1B_2E_3C"))
    )
    (comp (ref "V7")
      (value "TVS-NXP-PESD5V0L4UG")
      (footprint "SC70-5")
      (description "TVS, NXP, PESD3V3L4UG, SOT665")
      (libsource (lib "*") (part "TVS-NXP-PESD3V3L4UG"))
    )
    (comp (ref "V8")
      (value "BC817-25W")
      (footprint "SOT323-3N-CBE")
      (description "NPN Bipolar Transistor")
      (libsource (lib "Fotona") (part "TRANSISTOR_NPN"))
    )
    (comp (ref "V9")
      (value "BAT54CW")
      (footprint "FOTONA_IPC7351_DISCRETE:SOT323-3N")
      (description "Diode Schottky Common Chatode")
      (libsource (lib "Fotona") (part "D_SCH_CK_1A1-2A2-3K"))
    )
    (comp (ref "V10")
      (value "BAT54CW")
      (footprint "FOTONA_IPC7351_DISCRETE:SOT323-3N")
      (description "Diode Schottky Common Chatode")
      (libsource (lib "Fotona") (part "D_SCH_CK_1A1-2A2-3K"))
    )
    (comp (ref "V11")
      (value "TVS-NXP-PESD5V0L4UG")
      (footprint "SC70-5")
      (description "TVS, NXP, PESD3V3L4UG, SOT665")
      (libsource (lib "*") (part "TVS-NXP-PESD3V3L4UG"))
    )
    (comp (ref "V12")
      (value "BAT54CW")
      (footprint "FOTONA_IPC7351_DISCRETE:SOT323-3N")
      (description "Diode Schottky Common Chatode")
      (libsource (lib "Fotona") (part "D_SCH_CK_1A1-2A2-3K"))
    )
    (comp (ref "V13")
      (value "BAT54CW")
      (footprint "FOTONA_IPC7351_DISCRETE:SOT323-3N")
      (description "Diode Schottky Common Chatode")
      (libsource (lib "Fotona") (part "D_SCH_CK_1A1-2A2-3K"))
    )
    (comp (ref "V15")
      (value "BAT54CW")
      (footprint "FOTONA_IPC7351_DISCRETE:SOT323-3N")
      (description "Diode Schottky Common Chatode")
      (libsource (lib "Fotona") (part "D_SCH_CK_1A1-2A2-3K"))
    )
    (comp (ref "X1")
      (value "POWER")
      (footprint "CON_4.2_4X_V")
      (description "CONNECTOR")
      (libsource (lib "MA_CONNECT_1") (part "CON 4"))
    )
    (comp (ref "X2")
      (value "SYS PWR")
      (footprint "CON_3.0_2X_V_DUAL ROW")
      (description "Male 2mm Vertical Header 2 Pin")
      (libsource (lib "Fotona") (part "CON2"))
    )
    (comp (ref "X3") (value "LED1") (footprint "CON-PH_3PIN_JST") (libsource (lib "Device") (part "CON3")))
    (comp (ref "X4") (value "LED2") (footprint "CON-PH_3PIN_JST") (libsource (lib "Device") (part "CON3")))
    (comp (ref "X5")
      (value "FAN1")
      (footprint "MOLEX_47053-1000")
      (description "CONNECTOR")
      (libsource (lib "MA_CONNECT_1") (part "CON 4"))
    )
    (comp (ref "X6") (value "CAN1") (footprint "CON-PH_7PIN_JST") (libsource (lib "Mlk-sch") (part "CON7")))
    (comp (ref "X7") (value "CAN2") (footprint "CON-PH_7PIN_JST") (libsource (lib "Mlk-sch") (part "CON7")))
    (comp (ref "X8")
      (value "SOUND")
      (footprint "CON-MOLEX-53047-0310")
      (libsource (lib "Device") (part "CON3"))
    )
    (comp (ref "X9")
      (value "USB")
      (footprint "CON_uUSB_TOP")
      (description "USB B Micro  Female SMD Horizontal")
      (libsource (lib "Fotona") (part "CON6"))
    )
    (comp (ref "X10")
      (value "PUMP")
      (footprint "CON-PH_5PIN_JST")
      (description "CONNECTOR")
      (libsource (lib "MA_CONNECT_1") (part "CON 5"))
    )
    (comp (ref "X11")
      (value "SPARE")
      (footprint "CON-PH_8PIN_JST")
      (description "CONNECTOR")
      (libsource (lib "") (part "CON 8_1"))
    )
    (comp (ref "X12")
      (value "VALVE1")
      (footprint "CON-PH_6PIN_JST")
      (description "CONNECTOR")
      (libsource (lib "MA_CONNECT_1") (part "CON 6"))
    )
    (comp (ref "X13")
      (value "SYS DATA")
      (footprint "CON-MOLEX-53047-0810")
      (description "CONNECTOR")
      (libsource (lib "MA_CONNECT_1") (part "CON 8"))
    )
    (comp (ref "X14")
      (value "E. STOP")
      (footprint "CON-PH_2PIN_JST")
      (description "Right Angle Header SMD 2 pin")
      (libsource (lib "Fotona") (part "CON2"))
    )
    (comp (ref "X15")
      (value "FOOT / DOOR")
      (footprint "CON-PH_10PIN_JST")
      (description "CONNECTOR")
      (libsource (lib "MA_CONNECT_1") (part "CON 10"))
    )
    (comp (ref "X16")
      (value "EM / DL / CAN")
      (footprint "CON-MOLEX-53047-1010")
      (description "CONNECTOR")
      (libsource (lib "") (part "CON 10_1"))
    )
    (comp (ref "X17")
      (value "TEMP")
      (footprint "CON-PH_4PIN_JST")
      (description "CONNECTOR")
      (libsource (lib "MA_CONNECT_1") (part "CON 4"))
    )
    (comp (ref "X18")
      (value "VALVE2")
      (footprint "CON_3.0_2X_V_DUAL ROW")
      (description "Male 2mm Vertical Header 2 Pin")
      (libsource (lib "Fotona") (part "CON2"))
    )
    (comp (ref "X19")
      (value "SWD")
      (footprint "Mlk-pcb:CON-06-MALE-TH-2MM-VERTICAL")
      (description "Male 2.54mm Vertical Header 6 Pin")
      (fields (field (name "PART NUMBER") "100mil Header 1x6") (field (name "VOLTAGE") "250V"))
      (libsource (lib "Fotona") (part "CON6"))
    )
    (comp (ref "X20")
      (value "FAN2")
      (footprint "MOLEX_47053-1000")
      (description "CONNECTOR")
      (libsource (lib "MA_CONNECT_1") (part "CON 4"))
    )
    (comp (ref "X21")
      (value "BATT")
      (footprint "CON-MOLEX-53047-0210")
      (description "Right Angle Header SMD 2 pin")
      (libsource (lib "") (part "CON2_1"))
    )
  )
  (nets
    (net (code "1") (name "+3V3") (class "Default")
      (node (ref "C34") (pin "1") (pintype "passive"))
      (node (ref "C35") (pin "1") (pintype "passive"))
      (node (ref "C36") (pin "1") (pintype "passive"))
      (node (ref "C38") (pin "2") (pintype "passive"))
      (node (ref "C39") (pin "2") (pintype "passive"))
      (node (ref "C4") (pin "2") (pintype "passive"))
      (node (ref "C40") (pin "2") (pintype "passive"))
      (node (ref "IC1") (pin "3") (pinfunction "OUT_3") (pintype "power_in"))
      (node (ref "IC8") (pin "100") (pinfunction "Vdd_3_100") (pintype "power_in"))
      (node (ref "IC8") (pin "11") (pinfunction "Vdd_5_11") (pintype "power_in"))
      (node (ref "IC8") (pin "19") (pinfunction "Vdd12_19") (pintype "power_in"))
      (node (ref "IC8") (pin "28") (pinfunction "Vdd_4_28") (pintype "power_in"))
      (node (ref "IC8") (pin "50") (pinfunction "Vdd_1_50") (pintype "power_in"))
      (node (ref "IC8") (pin "75") (pinfunction "Vdd_2_75") (pintype "power_in"))
      (node (ref "V10") (pin "3") (pinfunction "K_3") (pintype "passive"))
      (node (ref "V12") (pin "2") (pinfunction "A2_2") (pintype "passive"))
      (node (ref "V13") (pin "3") (pinfunction "K_3") (pintype "passive"))
      (node (ref "V3") (pin "3") (pinfunction "K_3") (pintype "passive"))
      (node (ref "V9") (pin "3") (pinfunction "K_3") (pintype "passive"))
      (node (ref "X19") (pin "1") (pinfunction "1_1") (pintype "passive"))
    )
    (net (code "2") (name "+5V") (class "Default")
      (node (ref "A2") (pin "5") (pinfunction "Vout_5") (pintype "passive"))
      (node (ref "C15") (pin "2") (pintype "passive"))
      (node (ref "C18") (pin "2") (pintype "passive"))
      (node (ref "C27") (pin "1") (pintype "passive"))
      (node (ref "C3") (pin "2") (pintype "passive"))
      (node (ref "C30") (pin "2") (pintype "passive"))
      (node (ref "C46") (pin "1") (pintype "passive"))
      (node (ref "C59") (pin "P") (pinfunction "P_P") (pintype "passive"))
      (node (ref "C9") (pin "2") (pintype "passive"))
      (node (ref "H1") (pin "A") (pintype "passive"))
      (node (ref "H2") (pin "A") (pintype "passive"))
      (node (ref "H3") (pin "A") (pintype "passive"))
      (node (ref "H4") (pin "A") (pintype "passive"))
      (node (ref "H5") (pin "A") (pintype "passive"))
      (node (ref "H6") (pin "A") (pintype "passive"))
      (node (ref "H7") (pin "A") (pintype "passive"))
      (node (ref "H8") (pin "A") (pintype "passive"))
      (node (ref "IC1") (pin "1") (pinfunction "IN_1") (pintype "power_in"))
      (node (ref "IC10") (pin "16") (pinfunction "VCC_16") (pintype "power_in"))
      (node (ref "IC3") (pin "3") (pinfunction "VCC_3") (pintype "power_in"))
      (node (ref "IC4") (pin "6") (pinfunction "VDD_6") (pintype "power_in"))
      (node (ref "IC6") (pin "8") (pinfunction "VCC_8") (pintype "power_in"))
      (node (ref "JP1") (pin "2") (pintype "passive"))
      (node (ref "L19") (pin "2") (pinfunction "2_2") (pintype "passive"))
      (node (ref "R15") (pin "1") (pintype "passive"))
      (node (ref "R42") (pin "1") (pintype "passive"))
      (node (ref "V15") (pin "1") (pinfunction "A1_1") (pintype "passive"))
      (node (ref "X16") (pin "7") (pinfunction "7_7") (pintype "passive"))
      (node (ref "X3") (pin "1") (pinfunction "1_1") (pintype "passive"))
      (node (ref "X4") (pin "1") (pinfunction "1_1") (pintype "passive"))
      (node (ref "X6") (pin "1") (pinfunction "1_1") (pintype "passive"))
      (node (ref "X7") (pin "1") (pinfunction "1_1") (pintype "passive"))
    )
    (net (code "3") (name "+5VA") (class "Default")
      (node (ref "B1") (pin "2") (pinfunction "Vs_2") (pintype "passive"))
      (node (ref "B2") (pin "2") (pinfunction "Vs_2") (pintype "passive"))
      (node (ref "B3") (pin "2") (pinfunction "Vs_2") (pintype "passive"))
      (node (ref "B4") (pin "2") (pinfunction "Vs_2") (pintype "passive"))
      (node (ref "C13") (pin "1") (pintype "passive"))
      (node (ref "C26") (pin "1") (pintype "passive"))
      (node (ref "C49") (pin "1") (pintype "passive"))
      (node (ref "C51") (pin "1") (pintype "passive"))
      (node (ref "C53") (pin "1") (pintype "passive"))
      (node (ref "C55") (pin "1") (pintype "passive"))
      (node (ref "IC11") (pin "4") (pinfunction "OUT_4") (pintype "output"))
    )
    (net (code "4") (name "+12V") (class "Default")
      (node (ref "A1") (pin "5") (pinfunction "Vout_5") (pintype "passive"))
      (node (ref "C2") (pin "2") (pintype "passive"))
      (node (ref "F2") (pin "1") (pintype "passive"))
      (node (ref "JMP1") (pin "3") (pintype "passive"))
      (node (ref "R64") (pin "2") (pintype "passive"))
      (node (ref "X2") (pin "1") (pinfunction "1_1") (pintype "passive"))
    )
    (net (code "5") (name "/12Voff") (class "Default")
      (node (ref "IC8") (pin "92") (pinfunction "PB6//I2C1_SCL_92") (pintype "bidirectional"))
      (node (ref "R5") (pin "1") (pintype "passive"))
    )
    (net (code "6") (name "/AUDIO GND") (class "Default")
      (node (ref "C17") (pin "2") (pintype "passive"))
      (node (ref "X13") (pin "4") (pinfunction "4_4") (pintype "passive"))
    )
    (net (code "7") (name "/AUDIO IN1") (class "Default")
      (node (ref "C16") (pin "2") (pintype "passive"))
      (node (ref "X13") (pin "3") (pinfunction "3_3") (pintype "passive"))
    )
    (net (code "8") (name "/AUDIO IN2") (class "Default")
      (node (ref "X13") (pin "5") (pinfunction "5_5") (pintype "passive"))
    )
    (net (code "9") (name "/BOOT0") (class "Default")
      (node (ref "IC5") (pin "14") (pinfunction "CBUS3_14") (pintype "passive"))
      (node (ref "IC8") (pin "94") (pinfunction "BOOT0_94") (pintype "bidirectional"))
      (node (ref "R49") (pin "1") (pintype "passive"))
    )
    (net (code "10") (name "/BOOT1") (class "Default")
      (node (ref "IC8") (pin "37") (pinfunction "PB2/Boot1_37") (pintype "bidirectional"))
      (node (ref "R48") (pin "2") (pintype "passive"))
    )
    (net (code "11") (name "/CANH") (class "Default")
      (node (ref "IC3") (pin "7") (pinfunction "CANH_7") (pintype "passive"))
      (node (ref "R12") (pin "1") (pintype "passive"))
      (node (ref "X13") (pin "1") (pinfunction "1_1") (pintype "passive"))
      (node (ref "X16") (pin "1") (pinfunction "1_1") (pintype "passive"))
      (node (ref "X6") (pin "3") (pinfunction "3_3") (pintype "passive"))
      (node (ref "X7") (pin "3") (pinfunction "3_3") (pintype "passive"))
    )
    (net (code "12") (name "/CANL") (class "Default")
      (node (ref "IC3") (pin "6") (pinfunction "CANL_6") (pintype "passive"))
      (node (ref "R13") (pin "1") (pintype "passive"))
      (node (ref "X13") (pin "2") (pinfunction "2_2") (pintype "passive"))
      (node (ref "X16") (pin "3") (pinfunction "3_3") (pintype "passive"))
      (node (ref "X6") (pin "5") (pinfunction "5_5") (pintype "passive"))
      (node (ref "X7") (pin "5") (pinfunction "5_5") (pintype "passive"))
    )
    (net (code "13") (name "/CAN_RX") (class "Default")
      (node (ref "IC3") (pin "4") (pinfunction "RX_4") (pintype "output"))
      (node (ref "IC8") (pin "91") (pinfunction "PB5/CAN2_RX_91") (pintype "bidirectional"))
    )
    (net (code "14") (name "/CAN_TX") (class "Default")
      (node (ref "IC3") (pin "1") (pinfunction "TX_1") (pintype "input"))
      (node (ref "IC8") (pin "52") (pinfunction "PB13/CAN2_TX_52") (pintype "bidirectional"))
    )
    (net (code "15") (name "/DIODEsense1") (class "Default")
      (node (ref "IC8") (pin "33") (pinfunction "PC4/ADC12_IN14_33") (pintype "bidirectional"))
      (node (ref "IC8") (pin "53") (pinfunction "PB14/TIM12_CH1_53") (pintype "bidirectional"))
      (node (ref "L13") (pin "1") (pinfunction "1_1") (pintype "passive"))
      (node (ref "V13") (pin "2") (pinfunction "A2_2") (pintype "passive"))
    )
    (net (code "16") (name "/DIODEsense2") (class "Default")
      (node (ref "IC8") (pin "34") (pinfunction "PC5/ADC12_IN15_34") (pintype "bidirectional"))
      (node (ref "IC8") (pin "54") (pinfunction "PB15/TIM12_CH2_54") (pintype "bidirectional"))
      (node (ref "L14") (pin "1") (pinfunction "1_1") (pintype "passive"))
      (node (ref "V13") (pin "1") (pinfunction "A1_1") (pintype "passive"))
    )
    (net (code "17") (name "/DIODEstop") (class "Default")
      (node (ref "L2") (pin "1") (pinfunction "1_1") (pintype "passive"))
      (node (ref "V6") (pin "C") (pinfunction "C_C") (pintype "passive"))
      (node (ref "X6") (pin "2") (pinfunction "2_2") (pintype "passive"))
      (node (ref "X7") (pin "2") (pinfunction "2_2") (pintype "passive"))
    )
    (net (code "18") (name "/DOUT1") (class "Default")
      (node (ref "IC10") (pin "14") (pinfunction "~{DOUT1}_14") (pintype "output"))
      (node (ref "X15") (pin "8") (pinfunction "8_8") (pintype "passive"))
    )
    (net (code "19") (name "/FAN1_tacho") (class "Default")
      (node (ref "IC8") (pin "4") (pinfunction "PE5/TIM9_CH1_4") (pintype "bidirectional"))
      (node (ref "L20") (pin "1") (pinfunction "1_1") (pintype "passive"))
      (node (ref "V1") (pin "4") (pinfunction "4_4") (pintype "passive"))
    )
    (net (code "20") (name "/FAN2_tacho") (class "Default")
      (node (ref "IC8") (pin "5") (pinfunction "PE6/TIM9_CH2_5") (pintype "bidirectional"))
      (node (ref "L17") (pin "1") (pinfunction "1_1") (pintype "passive"))
      (node (ref "V1") (pin "5") (pinfunction "5_5") (pintype "passive"))
    )
    (net (code "21") (name "/FAN_RPM") (class "Default")
      (node (ref "IC8") (pin "95") (pinfunction "PB8/TIM10_CH1_95") (pintype "bidirectional"))
      (node (ref "L22") (pin "1") (pinfunction "1_1") (pintype "passive"))
      (node (ref "R63") (pin "1") (pintype "passive"))
      (node (ref "V1") (pin "1") (pinfunction "1_1") (pintype "passive"))
    )
    (net (code "22") (name "/FOOTSWactive") (class "Default")
      (node (ref "R9") (pin "1") (pintype "passive"))
      (node (ref "X15") (pin "5") (pinfunction "5_5") (pintype "passive"))
      (node (ref "X16") (pin "6") (pinfunction "6_6") (pintype "passive"))
      (node (ref "X6") (pin "6") (pinfunction "6_6") (pintype "passive"))
      (node (ref "X7") (pin "6") (pinfunction "6_6") (pintype "passive"))
    )
    (net (code "23") (name "/LED_1") (class "Default")
      (node (ref "IC8") (pin "59") (pinfunction "PD12/TIM4_CH1_59") (pintype "bidirectional"))
      (node (ref "R50") (pin "1") (pintype "passive"))
    )
    (net (code "24") (name "/LED_2") (class "Default")
      (node (ref "IC8") (pin "60") (pinfunction "PD13/TIM4_CH2_60") (pintype "bidirectional"))
      (node (ref "R51") (pin "1") (pintype "passive"))
    )
    (net (code "25") (name "/LED_BLUE1") (class "Default")
      (node (ref "IC8") (pin "84") (pinfunction "PD3_84") (pintype "bidirectional"))
      (node (ref "R30") (pin "1") (pintype "passive"))
    )
    (net (code "26") (name "/LED_BLUE2") (class "Default")
      (node (ref "IC8") (pin "88") (pinfunction "PD7_88") (pintype "bidirectional"))
      (node (ref "R34") (pin "1") (pintype "passive"))
    )
    (net (code "27") (name "/LED_GREEN1") (class "Default")
      (node (ref "IC8") (pin "82") (pinfunction "PD1_82") (pintype "bidirectional"))
      (node (ref "R28") (pin "1") (pintype "passive"))
    )
    (net (code "28") (name "/LED_GREEN2") (class "Default")
      (node (ref "IC8") (pin "86") (pinfunction "PD5_86") (pintype "bidirectional"))
      (node (ref "R32") (pin "1") (pintype "passive"))
    )
    (net (code "29") (name "/LED_RED1") (class "Default")
      (node (ref "IC8") (pin "81") (pinfunction "PD0_81") (pintype "bidirectional"))
      (node (ref "R27") (pin "1") (pintype "passive"))
    )
    (net (code "30") (name "/LED_RED2") (class "Default")
      (node (ref "IC8") (pin "85") (pinfunction "PD4_85") (pintype "bidirectional"))
      (node (ref "R31") (pin "1") (pintype "passive"))
    )
    (net (code "31") (name "/LED_YELLOW1") (class "Default")
      (node (ref "IC8") (pin "83") (pinfunction "PD2_83") (pintype "bidirectional"))
      (node (ref "R29") (pin "1") (pintype "passive"))
    )
    (net (code "32") (name "/LED_YELLOW2") (class "Default")
      (node (ref "IC8") (pin "87") (pinfunction "PD6_87") (pintype "bidirectional"))
      (node (ref "R33") (pin "1") (pintype "passive"))
    )
    (net (code "33") (name "/MCO") (class "Default")
      (node (ref "C45") (pin "2") (pintype "passive"))
      (node (ref "G1") (pin "2") (pinfunction "OSC2_2") (pintype "passive"))
      (node (ref "IC8") (pin "12") (pinfunction "OSC_IN_12") (pintype "input"))
    )
    (net (code "34") (name "/NRST") (class "Default")
      (node (ref "C31") (pin "1") (pintype "passive"))
      (node (ref "IC5") (pin "13") (pinfunction "CBUS2_13") (pintype "passive"))
      (node (ref "IC8") (pin "14") (pinfunction "NRST_14") (pintype "bidirectional"))
      (node (ref "X19") (pin "5") (pinfunction "5_5") (pintype "passive"))
    )
    (net (code "35") (name "/PUMP_CSENSE") (class "Default")
      (node (ref "IC8") (pin "23") (pinfunction "PA0/ADC123_IN0_23") (pintype "bidirectional"))
      (node (ref "R6") (pin "2") (pintype "passive"))
      (node (ref "V3") (pin "1") (pinfunction "A1_1") (pintype "passive"))
      (node (ref "V3") (pin "2") (pinfunction "A2_2") (pintype "passive"))
    )
    (net (code "36") (name "/PUMP_RPM") (class "Default")
      (node (ref "IC6") (pin "5") (pintype "input"))
      (node (ref "IC8") (pin "29") (pinfunction "PA4/DAC_OUT1/ADC12_IN4_29") (pintype "bidirectional"))
      (node (ref "R4") (pin "2") (pintype "passive"))
    )
    (net (code "37") (name "/PUMP_tacho") (class "Default")
      (node (ref "IC8") (pin "31") (pinfunction "PA6/ADC12_IN6/TIM3_CH1_31") (pintype "bidirectional"))
      (node (ref "V8") (pin "C") (pintype "passive"))
    )
    (net (code "38") (name "/Psense0") (class "Default")
      (node (ref "C50") (pin "1") (pintype "passive"))
      (node (ref "IC8") (pin "15") (pinfunction "PC0/ADC123_IN10_15") (pintype "bidirectional"))
      (node (ref "R55") (pin "1") (pintype "passive"))
      (node (ref "R56") (pin "2") (pintype "passive"))
    )
    (net (code "39") (name "/Psense1") (class "Default")
      (node (ref "C52") (pin "1") (pintype "passive"))
      (node (ref "IC8") (pin "16") (pinfunction "PC1/ADC123_IN11_16") (pintype "bidirectional"))
      (node (ref "R57") (pin "1") (pintype "passive"))
      (node (ref "R58") (pin "2") (pintype "passive"))
    )
    (net (code "40") (name "/Psense2") (class "Default")
      (node (ref "C54") (pin "1") (pintype "passive"))
      (node (ref "IC8") (pin "17") (pinfunction "PC2/ADC123_IN12_17") (pintype "bidirectional"))
      (node (ref "R59") (pin "1") (pintype "passive"))
      (node (ref "R60") (pin "2") (pintype "passive"))
    )
    (net (code "41") (name "/Psense3") (class "Default")
      (node (ref "C56") (pin "1") (pintype "passive"))
      (node (ref "IC8") (pin "18") (pinfunction "PC3/ADC123_IN13_18") (pintype "bidirectional"))
      (node (ref "R61") (pin "1") (pintype "passive"))
      (node (ref "R62") (pin "2") (pintype "passive"))
    )
    (net (code "42") (name "/RIN1") (class "Default")
      (node (ref "IC10") (pin "13") (pinfunction "RIN1_13") (pintype "input"))
      (node (ref "X15") (pin "7") (pinfunction "7_7") (pintype "passive"))
    )
    (net (code "43") (name "/SWCLK") (class "Default")
      (node (ref "IC8") (pin "76") (pinfunction "PA14_76") (pintype "bidirectional"))
      (node (ref "X19") (pin "2") (pinfunction "2_2") (pintype "passive"))
    )
    (net (code "44") (name "/SWDIO") (class "Default")
      (node (ref "IC8") (pin "72") (pinfunction "PA13_72") (pintype "bidirectional"))
      (node (ref "X19") (pin "4") (pinfunction "4_4") (pintype "passive"))
    )
    (net (code "45") (name "/SWO") (class "Default")
      (node (ref "IC8") (pin "89") (pinfunction "PB3/TIM2_CH2_89") (pintype "bidirectional"))
      (node (ref "X19") (pin "6") (pinfunction "6_6") (pintype "passive"))
    )
    (net (code "46") (name "/SYS_SHG") (class "Default")
      (node (ref "IC8") (pin "90") (pinfunction "PB4_90") (pintype "bidirectional"))
      (node (ref "R14") (pin "2") (pintype "passive"))
    )
    (net (code "47") (name "/TIM1_CH1") (class "Default")
      (node (ref "IC7") (pin "4") (pinfunction "I3_4") (pintype "passive"))
      (node (ref "IC8") (pin "40") (pinfunction "PE9/TIM1_CH1_40") (pintype "bidirectional"))
    )
    (net (code "48") (name "/TIM1_CH2") (class "Default")
      (node (ref "IC7") (pin "3") (pinfunction "I2_3") (pintype "passive"))
      (node (ref "IC8") (pin "42") (pinfunction "PE11/TIM1_CH2_42") (pintype "bidirectional"))
    )
    (net (code "49") (name "/TIM1_CH3") (class "Default")
      (node (ref "IC7") (pin "2") (pinfunction "I1_2") (pintype "passive"))
      (node (ref "IC8") (pin "44") (pinfunction "PE13/TIM1_CH3_44") (pintype "bidirectional"))
    )
    (net (code "50") (name "/TIM1_CH4") (class "Default")
      (node (ref "IC7") (pin "1") (pinfunction "I0_1") (pintype "passive"))
      (node (ref "IC8") (pin "45") (pinfunction "PE14/TIM1_CH4_45") (pintype "bidirectional"))
    )
    (net (code "51") (name "/TIM8_CH1") (class "Default")
      (node (ref "IC7") (pin "5") (pinfunction "I4_5") (pintype "passive"))
      (node (ref "IC8") (pin "63") (pinfunction "PC6/TIM8_CH1_63") (pintype "bidirectional"))
    )
    (net (code "52") (name "/TIM8_CH2") (class "Default")
      (node (ref "IC7") (pin "6") (pinfunction "I5_6") (pintype "passive"))
      (node (ref "IC8") (pin "64") (pinfunction "PC7/TIM8_CH2_64") (pintype "bidirectional"))
    )
    (net (code "53") (name "/TIM8_CH3") (class "Default")
      (node (ref "IC7") (pin "7") (pinfunction "I6_7") (pintype "passive"))
      (node (ref "IC8") (pin "65") (pinfunction "PC8/TIM8_CH3_65") (pintype "bidirectional"))
    )
    (net (code "54") (name "/TIM8_CH4") (class "Default")
      (node (ref "IC7") (pin "8") (pinfunction "I7_8") (pintype "passive"))
      (node (ref "IC8") (pin "66") (pinfunction "PC9/TIM8_CH4_66") (pintype "bidirectional"))
    )
    (net (code "55") (name "/TempH2O_1") (class "Default")
      (node (ref "C47") (pin "1") (pintype "passive"))
      (node (ref "IC8") (pin "24") (pinfunction "PA1/ADC123_IN1_24") (pintype "bidirectional"))
      (node (ref "R53") (pin "1") (pintype "passive"))
      (node (ref "X17") (pin "1") (pinfunction "1_1") (pintype "passive"))
    )
    (net (code "56") (name "/TempH2O_2") (class "Default")
      (node (ref "C48") (pin "1") (pintype "passive"))
      (node (ref "IC8") (pin "25") (pinfunction "PA2/ADC123_IN2_25") (pintype "bidirectional"))
      (node (ref "R54") (pin "1") (pintype "passive"))
      (node (ref "X17") (pin "3") (pinfunction "3_3") (pintype "passive"))
    )
    (net (code "57") (name "/UART0_RXD") (class "Default")
      (node (ref "JP2") (pin "1") (pintype "passive"))
      (node (ref "X13") (pin "7") (pinfunction "7_7") (pintype "passive"))
    )
    (net (code "58") (name "/UART0_TXD") (class "Default")
      (node (ref "JP3") (pin "1") (pintype "passive"))
      (node (ref "X13") (pin "8") (pinfunction "8_8") (pintype "passive"))
    )
    (net (code "59") (name "/USART1_RX") (class "Default")
      (node (ref "IC8") (pin "69") (pinfunction "PA10/USART1_RX_69") (pintype "bidirectional"))
      (node (ref "JP2") (pin "3") (pintype "passive"))
    )
    (net (code "60") (name "/USART1_TX") (class "Default")
      (node (ref "IC8") (pin "68") (pinfunction "PA9/USART1_TX_68") (pintype "bidirectional"))
      (node (ref "JP3") (pin "3") (pintype "passive"))
    )
    (net (code "61") (name "/USART3_RX") (class "Default")
      (node (ref "IC10") (pin "12") (pinfunction "~{ROUT1}_12") (pintype "output"))
      (node (ref "IC8") (pin "79") (pinfunction "PC11/USART3_RX_79") (pintype "bidirectional"))
    )
    (net (code "62") (name "/USART3_TX") (class "Default")
      (node (ref "IC10") (pin "11") (pinfunction "DIN1_11") (pintype "input"))
      (node (ref "IC8") (pin "78") (pinfunction "PC10/USART3_TX_78") (pintype "bidirectional"))
    )
    (net (code "63") (name "/USBDM") (class "Default")
      (node (ref "C22") (pin "2") (pintype "passive"))
      (node (ref "IC5") (pin "16") (pinfunction "USBDM_16") (pintype "passive"))
      (node (ref "R20") (pin "1") (pintype "passive"))
    )
    (net (code "64") (name "/USBDP") (class "Default")
      (node (ref "C24") (pin "1") (pintype "passive"))
      (node (ref "IC5") (pin "15") (pinfunction "USBDP_15") (pintype "passive"))
      (node (ref "R21") (pin "1") (pintype "passive"))
    )
    (net (code "65") (name "/USBPWR#") (class "Default")
      (node (ref "IC5") (pin "12") (pinfunction "CBUS4_12") (pintype "passive"))
      (node (ref "R26") (pin "2") (pintype "passive"))
    )
    (net (code "66") (name "/USB_RXLED") (class "Default")
      (node (ref "IC5") (pin "22") (pinfunction "CBUS1_22") (pintype "passive"))
      (node (ref "R25") (pin "2") (pintype "passive"))
    )
    (net (code "67") (name "/USB_TXLED") (class "Default")
      (node (ref "IC5") (pin "23") (pinfunction "CBUS0_23") (pintype "passive"))
      (node (ref "R24") (pin "2") (pintype "passive"))
    )
    (net (code "68") (name "/cwbBUTTON") (class "Default")
      (node (ref "L12") (pin "1") (pinfunction "1_1") (pintype "passive"))
      (node (ref "R36") (pin "1") (pintype "passive"))
      (node (ref "V11") (pin "1") (pinfunction "1_1") (pintype "passive"))
      (node (ref "V6") (pin "E") (pinfunction "E_E") (pintype "passive"))
    )
    (net (code "69") (name "/cwbDOOR") (class "Default")
      (node (ref "L1") (pin "1") (pinfunction "1_1") (pintype "passive"))
      (node (ref "L16") (pin "1") (pinfunction "1_1") (pintype "passive"))
      (node (ref "R37") (pin "1") (pintype "passive"))
      (node (ref "V11") (pin "3") (pinfunction "3_3") (pintype "passive"))
    )
    (net (code "70") (name "/cwbENGM") (class "Default")
      (node (ref "L15") (pin "1") (pinfunction "1_1") (pintype "passive"))
      (node (ref "L21") (pin "1") (pinfunction "1_1") (pintype "passive"))
      (node (ref "R38") (pin "1") (pintype "passive"))
      (node (ref "V4") (pin "1") (pinfunction "1_1") (pintype "passive"))
    )
    (net (code "71") (name "24V") (class "Default")
      (node (ref "A1") (pin "2") (pinfunction "Vin_2") (pintype "passive"))
      (node (ref "A2") (pin "2") (pinfunction "Vin_2") (pintype "passive"))
      (node (ref "C1") (pin "1") (pintype "passive"))
      (node (ref "C25") (pin "1") (pintype "passive"))
      (node (ref "C29") (pin "1") (pintype "passive"))
      (node (ref "F1") (pin "2") (pinfunction "2_2") (pintype "passive"))
      (node (ref "IC7") (pin "10") (pinfunction "PWR_10") (pintype "passive"))
      (node (ref "JMP1") (pin "1") (pintype "passive"))
      (node (ref "R46") (pin "2") (pintype "passive"))
      (node (ref "R7") (pin "2") (pintype "passive"))
      (node (ref "X10") (pin "5") (pinfunction "5_5") (pintype "passive"))
      (node (ref "X11") (pin "2") (pinfunction "2_2") (pintype "passive"))
      (node (ref "X11") (pin "4") (pinfunction "4_4") (pintype "passive"))
      (node (ref "X11") (pin "6") (pinfunction "6_6") (pintype "passive"))
      (node (ref "X11") (pin "8") (pinfunction "8_8") (pintype "passive"))
      (node (ref "X12") (pin "2") (pinfunction "2_2") (pintype "passive"))
      (node (ref "X12") (pin "4") (pinfunction "4_4") (pintype "passive"))
      (node (ref "X12") (pin "6") (pinfunction "6_6") (pintype "passive"))
      (node (ref "X18") (pin "1") (pinfunction "1_1") (pintype "passive"))
    )
    (net (code "72") (name "Agnd") (class "Default")
      (node (ref "B1") (pin "3") (pinfunction "GND_3") (pintype "passive"))
      (node (ref "B2") (pin "3") (pinfunction "GND_3") (pintype "passive"))
      (node (ref "B3") (pin "3") (pinfunction "GND_3") (pintype "passive"))
      (node (ref "B4") (pin "3") (pinfunction "GND_3") (pintype "passive"))
      (node (ref "C12") (pin "2") (pintype "passive"))
      (node (ref "C26") (pin "2") (pintype "passive"))
      (node (ref "C41") (pin "2") (pintype "passive"))
      (node (ref "C42") (pin "2") (pintype "passive"))
      (node (ref "C43") (pin "2") (pintype "passive"))
      (node (ref "C47") (pin "2") (pintype "passive"))
      (node (ref "C48") (pin "2") (pintype "passive"))
      (node (ref "C49") (pin "2") (pintype "passive"))
      (node (ref "C50") (pin "2") (pintype "passive"))
      (node (ref "C51") (pin "2") (pintype "passive"))
      (node (ref "C52") (pin "2") (pintype "passive"))
      (node (ref "C53") (pin "2") (pintype "passive"))
      (node (ref "C54") (pin "2") (pintype "passive"))
      (node (ref "C55") (pin "2") (pintype "passive"))
      (node (ref "C56") (pin "2") (pintype "passive"))
      (node (ref "IC11") (pin "1") (pinfunction "GND_1") (pintype "passive"))
      (node (ref "IC8") (pin "20") (pinfunction "VssA_20") (pintype "input"))
      (node (ref "IC9") (pin "3") (pinfunction "GND_3") (pintype "power_in"))
      (node (ref "J4") (pin "2") (pintype "passive"))
      (node (ref "R43") (pin "1") (pintype "passive"))
      (node (ref "R45") (pin "2") (pintype "passive"))
      (node (ref "R47") (pin "1") (pintype "passive"))
      (node (ref "R56") (pin "1") (pintype "passive"))
      (node (ref "R58") (pin "1") (pintype "passive"))
      (node (ref "R60") (pin "1") (pintype "passive"))
      (node (ref "R62") (pin "1") (pintype "passive"))
      (node (ref "X17") (pin "2") (pinfunction "2_2") (pintype "passive"))
      (node (ref "X17") (pin "4") (pinfunction "4_4") (pintype "passive"))
    )
    (net (code "73") (name "EARTH") (class "Default")
      (node (ref "J2") (pin "2") (pintype "passive"))
      (node (ref "J3") (pin "1") (pintype "passive"))
      (node (ref "TP1") (pin "1") (pinfunction "1_1") (pintype "passive"))
    )
    (net (code "74") (name "GND") (class "Default")
      (node (ref "C10") (pin "2") (pintype "passive"))
      (node (ref "C11") (pin "2") (pintype "passive"))
      (node (ref "C14") (pin "1") (pintype "passive"))
      (node (ref "C15") (pin "1") (pintype "passive"))
      (node (ref "C18") (pin "1") (pintype "passive"))
      (node (ref "C19") (pin "2") (pintype "passive"))
      (node (ref "C20") (pin "2") (pintype "passive"))
      (node (ref "C21") (pin "1") (pintype "passive"))
      (node (ref "C22") (pin "1") (pintype "passive"))
      (node (ref "C23") (pin "1") (pintype "passive"))
      (node (ref "C24") (pin "2") (pintype "passive"))
      (node (ref "C27") (pin "2") (pintype "passive"))
      (node (ref "C3") (pin "1") (pintype "passive"))
      (node (ref "C30") (pin "1") (pintype "passive"))
      (node (ref "C31") (pin "2") (pintype "passive"))
      (node (ref "C32") (pin "2") (pintype "passive"))
      (node (ref "C33") (pin "2") (pintype "passive"))
      (node (ref "C34") (pin "2") (pintype "passive"))
      (node (ref "C35") (pin "2") (pintype "passive"))
      (node (ref "C36") (pin "2") (pintype "passive"))
      (node (ref "C37") (pin "2") (pintype "passive"))
      (node (ref "C38") (pin "1") (pintype "passive"))
      (node (ref "C39") (pin "1") (pintype "passive"))
      (node (ref "C4") (pin "1") (pintype "passive"))
      (node (ref "C40") (pin "1") (pintype "passive"))
      (node (ref "C44") (pin "1") (pintype "passive"))
      (node (ref "C45") (pin "1") (pintype "passive"))
      (node (ref "C46") (pin "2") (pintype "passive"))
      (node (ref "C57") (pin "2") (pintype "passive"))
      (node (ref "C58") (pin "2") (pintype "passive"))
      (node (ref "C59") (pin "M") (pinfunction "M_M") (pintype "passive"))
      (node (ref "C7") (pin "1") (pintype "passive"))
      (node (ref "C8") (pin "1") (pintype "passive"))
      (node (ref "C9") (pin "1") (pintype "passive"))
      (node (ref "G3") (pin "M") (pinfunction "-_M") (pintype "passive"))
      (node (ref "IC1") (pin "2") (pinfunction "GND_2") (pintype "power_in"))
      (node (ref "IC10") (pin "15") (pinfunction "GND_15") (pintype "power_in"))
      (node (ref "IC2") (pin "11") (pinfunction "E_11") (pintype "passive"))
      (node (ref "IC2") (pin "13") (pinfunction "E_13") (pintype "passive"))
      (node (ref "IC2") (pin "15") (pinfunction "E_15") (pintype "passive"))
      (node (ref "IC2") (pin "9") (pinfunction "E_9") (pintype "passive"))
      (node (ref "IC3") (pin "2") (pinfunction "GND_2") (pintype "power_in"))
      (node (ref "IC3") (pin "8") (pinfunction "STB_8") (pintype "input"))
      (node (ref "IC4") (pin "2") (pinfunction "NC_2") (pintype "passive"))
      (node (ref "IC4") (pin "7") (pinfunction "GND_7") (pintype "power_in"))
      (node (ref "IC4") (pin "9") (pinfunction "EP_9") (pintype "power_in"))
      (node (ref "IC5") (pin "18") (pinfunction "GND_18") (pintype "passive"))
      (node (ref "IC5") (pin "21") (pinfunction "GND_21") (pintype "passive"))
      (node (ref "IC5") (pin "25") (pinfunction "AGND_25") (pintype "passive"))
      (node (ref "IC5") (pin "26") (pinfunction "TEST_26") (pintype "passive"))
      (node (ref "IC5") (pin "7") (pinfunction "GND_7") (pintype "passive"))
      (node (ref "IC6") (pin "4") (pinfunction "VEE_4") (pintype "power_in"))
      (node (ref "IC8") (pin "10") (pinfunction "Vss_5_10") (pintype "power_in"))
      (node (ref "IC8") (pin "27") (pinfunction "Vss_4_27") (pintype "power_in"))
      (node (ref "IC8") (pin "74") (pinfunction "Vss_2_74") (pintype "power_in"))
      (node (ref "IC8") (pin "99") (pinfunction "RFU_99") (pintype "passive"))
      (node (ref "J3") (pin "2") (pintype "passive"))
      (node (ref "J4") (pin "1") (pintype "passive"))
      (node (ref "R23") (pin "1") (pintype "passive"))
      (node (ref "R3") (pin "2") (pintype "passive"))
      (node (ref "R4") (pin "1") (pintype "passive"))
      (node (ref "R48") (pin "1") (pintype "passive"))
      (node (ref "R49") (pin "2") (pintype "passive"))
      (node (ref "V11") (pin "2") (pinfunction "2_2") (pintype "passive"))
      (node (ref "V4") (pin "2") (pinfunction "2_2") (pintype "passive"))
      (node (ref "V7") (pin "2") (pinfunction "2_2") (pintype "passive"))
      (node (ref "X13") (pin "6") (pinfunction "6_6") (pintype "passive"))
      (node (ref "X16") (pin "4") (pinfunction "4_4") (pintype "passive"))
      (node (ref "X19") (pin "3") (pinfunction "3_3") (pintype "passive"))
      (node (ref "X21") (pin "2") (pinfunction "2_2") (pintype "passive"))
      (node (ref "X3") (pin "3") (pinfunction "3_3") (pintype "passive"))
      (node (ref "X4") (pin "3") (pinfunction "3_3") (pintype "passive"))
      (node (ref "X6") (pin "4") (pinfunction "4_4") (pintype "passive"))
      (node (ref "X7") (pin "4") (pinfunction "4_4") (pintype "passive"))
      (node (ref "X9") (pin "5") (pinfunction "5_5") (pintype "passive"))
      (node (ref "X9") (pin "6") (pinfunction "6_6") (pintype "passive"))
    )
    (net (code "75") (name "Net-(A1-ON{slash}OFF)") (class "Default")
      (node (ref "A1") (pin "1") (pinfunction "ON/OFF_1") (pintype "passive"))
      (node (ref "V2") (pin "C") (pintype "passive"))
    )
    (net (code "76") (name "Net-(A1-TRIM)") (class "Default")
      (node (ref "A1") (pin "4") (pinfunction "TRIM_4") (pintype "passive"))
      (node (ref "R1") (pin "1") (pintype "passive"))
    )
    (net (code "77") (name "Net-(B1-OUT)") (class "Default")
      (node (ref "B1") (pin "4") (pinfunction "OUT_4") (pintype "passive"))
      (node (ref "R55") (pin "2") (pintype "passive"))
    )
    (net (code "78") (name "Net-(B2-OUT)") (class "Default")
      (node (ref "B2") (pin "4") (pinfunction "OUT_4") (pintype "passive"))
      (node (ref "R57") (pin "2") (pintype "passive"))
    )
    (net (code "79") (name "Net-(B3-OUT)") (class "Default")
      (node (ref "B3") (pin "4") (pinfunction "OUT_4") (pintype "passive"))
      (node (ref "R59") (pin "2") (pintype "passive"))
    )
    (net (code "80") (name "Net-(B4-OUT)") (class "Default")
      (node (ref "B4") (pin "4") (pinfunction "OUT_4") (pintype "passive"))
      (node (ref "R61") (pin "2") (pintype "passive"))
    )
    (net (code "81") (name "Net-(C10-Pad1)") (class "Default")
      (node (ref "C10") (pin "1") (pintype "passive"))
      (node (ref "R50") (pin "2") (pintype "passive"))
      (node (ref "X3") (pin "2") (pinfunction "2_2") (pintype "passive"))
    )
    (net (code "82") (name "Net-(C11-Pad1)") (class "Default")
      (node (ref "C11") (pin "1") (pintype "passive"))
      (node (ref "R51") (pin "2") (pintype "passive"))
      (node (ref "X4") (pin "2") (pinfunction "2_2") (pintype "passive"))
    )
    (net (code "83") (name "Net-(C19-Pad1)") (class "Default")
      (node (ref "C19") (pin "1") (pintype "passive"))
      (node (ref "L3") (pin "1") (pinfunction "1_1") (pintype "passive"))
      (node (ref "R22") (pin "1") (pintype "passive"))
      (node (ref "V7") (pin "4") (pinfunction "4_4") (pintype "passive"))
      (node (ref "X9") (pin "1") (pinfunction "1_1") (pintype "passive"))
    )
    (net (code "84") (name "Net-(C28-Pad1)") (class "Default")
      (node (ref "C28") (pin "1") (pintype "passive"))
      (node (ref "IC6") (pin "1") (pintype "output"))
      (node (ref "R41") (pin "2") (pintype "passive"))
      (node (ref "R6") (pin "1") (pintype "passive"))
    )
    (net (code "85") (name "Net-(C28-Pad2)") (class "Default")
      (node (ref "C28") (pin "2") (pintype "passive"))
      (node (ref "IC6") (pin "2") (pintype "input"))
      (node (ref "R40") (pin "2") (pintype "passive"))
      (node (ref "R41") (pin "1") (pintype "passive"))
    )
    (net (code "86") (name "Net-(F1-Pad1)") (class "Default")
      (node (ref "F1") (pin "1") (pinfunction "1_1") (pintype "passive"))
      (node (ref "X1") (pin "1") (pinfunction "1_1") (pintype "passive"))
      (node (ref "X1") (pin "3") (pinfunction "3_3") (pintype "passive"))
    )
    (net (code "87") (name "Net-(F2-Pad2)") (class "Default")
      (node (ref "F2") (pin "2") (pintype "passive"))
      (node (ref "IC2") (pin "1") (pinfunction "A_1") (pintype "passive"))
      (node (ref "IC2") (pin "3") (pinfunction "A_3") (pintype "passive"))
      (node (ref "IC2") (pin "5") (pinfunction "A_5") (pintype "passive"))
      (node (ref "IC2") (pin "7") (pinfunction "A_7") (pintype "passive"))
      (node (ref "R44") (pin "2") (pintype "passive"))
      (node (ref "X15") (pin "1") (pinfunction "1_1") (pintype "passive"))
    )
    (net (code "88") (name "Net-(G1-OSC1)") (class "Default")
      (node (ref "C44") (pin "2") (pintype "passive"))
      (node (ref "G1") (pin "1") (pinfunction "OSC1_1") (pintype "passive"))
      (node (ref "R52") (pin "1") (pintype "passive"))
    )
    (net (code "89") (name "Net-(G3-+)") (class "Default")
      (node (ref "G3") (pin "P") (pinfunction "+_P") (pintype "passive"))
      (node (ref "V12") (pin "1") (pinfunction "A1_1") (pintype "passive"))
      (node (ref "X21") (pin "1") (pinfunction "1_1") (pintype "passive"))
    )
    (net (code "90") (name "Net-(H1-PadK)") (class "Default")
      (node (ref "H1") (pin "K") (pintype "passive"))
      (node (ref "R27") (pin "2") (pintype "passive"))
    )
    (net (code "91") (name "Net-(H2-PadK)") (class "Default")
      (node (ref "H2") (pin "K") (pintype "passive"))
      (node (ref "R28") (pin "2") (pintype "passive"))
    )
    (net (code "92") (name "Net-(H3-PadK)") (class "Default")
      (node (ref "H3") (pin "K") (pintype "passive"))
      (node (ref "R29") (pin "2") (pintype "passive"))
    )
    (net (code "93") (name "Net-(H4-PadK)") (class "Default")
      (node (ref "H4") (pin "K") (pintype "passive"))
      (node (ref "R30") (pin "2") (pintype "passive"))
    )
    (net (code "94") (name "Net-(H5-PadK)") (class "Default")
      (node (ref "H5") (pin "K") (pintype "passive"))
      (node (ref "R31") (pin "2") (pintype "passive"))
    )
    (net (code "95") (name "Net-(H6-PadK)") (class "Default")
      (node (ref "H6") (pin "K") (pintype "passive"))
      (node (ref "R32") (pin "2") (pintype "passive"))
    )
    (net (code "96") (name "Net-(H7-PadK)") (class "Default")
      (node (ref "H7") (pin "K") (pintype "passive"))
      (node (ref "R33") (pin "2") (pintype "passive"))
    )
    (net (code "97") (name "Net-(H8-PadK)") (class "Default")
      (node (ref "H8") (pin "K") (pintype "passive"))
      (node (ref "R34") (pin "2") (pintype "passive"))
    )
    (net (code "98") (name "Net-(H9-PadK)") (class "Default")
      (node (ref "H9") (pin "K") (pinfunction "K_K") (pintype "passive"))
      (node (ref "R24") (pin "1") (pintype "passive"))
    )
    (net (code "99") (name "Net-(H10-PadK)") (class "Default")
      (node (ref "H10") (pin "K") (pinfunction "K_K") (pintype "passive"))
      (node (ref "R25") (pin "1") (pintype "passive"))
    )
    (net (code "100") (name "Net-(H11-PadK)") (class "Default")
      (node (ref "H11") (pin "K") (pinfunction "K_K") (pintype "passive"))
      (node (ref "R26") (pin "1") (pintype "passive"))
    )
    (net (code "101") (name "Net-(H12-PadA)") (class "Default")
      (node (ref "H12") (pin "A") (pintype "passive"))
      (node (ref "V5") (pin "A") (pintype "passive"))
    )
    (net (code "102") (name "Net-(IC2-K-Pad2)") (class "Default")
      (node (ref "IC2") (pin "2") (pinfunction "K_2") (pintype "passive"))
      (node (ref "R8") (pin "2") (pintype "passive"))
    )
    (net (code "103") (name "Net-(IC2-K-Pad4)") (class "Default")
      (node (ref "IC2") (pin "4") (pinfunction "K_4") (pintype "passive"))
      (node (ref "R9") (pin "2") (pintype "passive"))
    )
    (net (code "104") (name "Net-(IC2-K-Pad6)") (class "Default")
      (node (ref "IC2") (pin "6") (pinfunction "K_6") (pintype "passive"))
      (node (ref "R10") (pin "2") (pintype "passive"))
    )
    (net (code "105") (name "Net-(IC2-K-Pad8)") (class "Default")
      (node (ref "IC2") (pin "8") (pinfunction "K_8") (pintype "passive"))
      (node (ref "R11") (pin "2") (pintype "passive"))
    )
    (net (code "106") (name "Net-(IC3-SPLIT)") (class "Default")
      (node (ref "C14") (pin "2") (pintype "passive"))
      (node (ref "IC3") (pin "5") (pinfunction "SPLIT_5") (pintype "passive"))
      (node (ref "R12") (pin "2") (pintype "passive"))
      (node (ref "R13") (pin "2") (pintype "passive"))
    )
    (net (code "107") (name "Net-(IC4-IN+)") (class "Default")
      (node (ref "C16") (pin "1") (pintype "passive"))
      (node (ref "IC4") (pin "3") (pinfunction "IN+_3") (pintype "input"))
    )
    (net (code "108") (name "Net-(IC4-IN-)") (class "Default")
      (node (ref "C17") (pin "1") (pintype "passive"))
      (node (ref "IC4") (pin "4") (pinfunction "IN-_4") (pintype "input"))
    )
    (net (code "109") (name "Net-(IC4-OUT+)") (class "Default")
      (node (ref "IC4") (pin "5") (pinfunction "OUT+_5") (pintype "output"))
      (node (ref "X8") (pin "1") (pinfunction "1_1") (pintype "passive"))
    )
    (net (code "110") (name "Net-(IC4-OUT-)") (class "Default")
      (node (ref "IC4") (pin "8") (pinfunction "OUT-_8") (pintype "passive"))
      (node (ref "X8") (pin "3") (pinfunction "3_3") (pintype "passive"))
    )
    (net (code "111") (name "Net-(IC4-~{SD})") (class "Default")
      (node (ref "IC4") (pin "1") (pinfunction "~{SD}_1") (pintype "passive"))
      (node (ref "R15") (pin "2") (pintype "passive"))
    )
    (net (code "112") (name "Net-(IC5-RXD)") (class "Default")
      (node (ref "IC5") (pin "5") (pinfunction "RXD_5") (pintype "passive"))
      (node (ref "JP3") (pin "2") (pintype "passive"))
    )
    (net (code "113") (name "Net-(IC5-TXD)") (class "Default")
      (node (ref "IC5") (pin "1") (pinfunction "TXD_1") (pintype "passive"))
      (node (ref "JP2") (pin "2") (pintype "passive"))
    )
    (net (code "114") (name "Net-(IC5-VCC)") (class "Default")
      (node (ref "C20") (pin "1") (pintype "passive"))
      (node (ref "C21") (pin "2") (pintype "passive"))
      (node (ref "IC5") (pin "20") (pinfunction "VCC_20") (pintype "passive"))
      (node (ref "V15") (pin "3") (pinfunction "K_3") (pintype "passive"))
    )
    (net (code "115") (name "Net-(IC5-~{RESET})") (class "Default")
      (node (ref "IC5") (pin "19") (pinfunction "~{RESET}_19") (pintype "passive"))
      (node (ref "R22") (pin "2") (pintype "passive"))
      (node (ref "R23") (pin "2") (pintype "passive"))
    )
    (net (code "116") (name "Net-(IC6-Pad3)") (class "Default")
      (node (ref "IC6") (pin "3") (pintype "input"))
      (node (ref "R39") (pin "2") (pintype "passive"))
      (node (ref "X10") (pin "1") (pinfunction "1_1") (pintype "passive"))
    )
    (net (code "117") (name "Net-(IC6-Pad6)") (class "Default")
      (node (ref "IC6") (pin "6") (pintype "input"))
      (node (ref "R2") (pin "2") (pintype "passive"))
      (node (ref "R3") (pin "1") (pintype "passive"))
    )
    (net (code "118") (name "Net-(IC6-Pad7)") (class "Default")
      (node (ref "IC6") (pin "7") (pintype "output"))
      (node (ref "R2") (pin "1") (pintype "passive"))
      (node (ref "X10") (pin "4") (pinfunction "4_4") (pintype "passive"))
    )
    (net (code "119") (name "Net-(IC7-O0)") (class "Default")
      (node (ref "IC7") (pin "18") (pinfunction "O0_18") (pintype "passive"))
      (node (ref "L4") (pin "1") (pinfunction "1_1") (pintype "passive"))
    )
    (net (code "120") (name "Net-(IC7-O1)") (class "Default")
      (node (ref "IC7") (pin "17") (pinfunction "O1_17") (pintype "passive"))
      (node (ref "L5") (pin "1") (pinfunction "1_1") (pintype "passive"))
    )
    (net (code "121") (name "Net-(IC7-O2)") (class "Default")
      (node (ref "IC7") (pin "16") (pinfunction "O2_16") (pintype "passive"))
      (node (ref "L6") (pin "1") (pinfunction "1_1") (pintype "passive"))
    )
    (net (code "122") (name "Net-(IC7-O3)") (class "Default")
      (node (ref "IC7") (pin "15") (pinfunction "O3_15") (pintype "passive"))
      (node (ref "L7") (pin "1") (pinfunction "1_1") (pintype "passive"))
    )
    (net (code "123") (name "Net-(IC7-O4)") (class "Default")
      (node (ref "IC7") (pin "14") (pinfunction "O4_14") (pintype "passive"))
      (node (ref "L8") (pin "1") (pinfunction "1_1") (pintype "passive"))
    )
    (net (code "124") (name "Net-(IC7-O5)") (class "Default")
      (node (ref "IC7") (pin "13") (pinfunction "O5_13") (pintype "passive"))
      (node (ref "L9") (pin "1") (pinfunction "1_1") (pintype "passive"))
    )
    (net (code "125") (name "Net-(IC7-O6)") (class "Default")
      (node (ref "IC7") (pin "12") (pinfunction "O6_12") (pintype "passive"))
      (node (ref "L10") (pin "1") (pinfunction "1_1") (pintype "passive"))
    )
    (net (code "126") (name "Net-(IC7-O7)") (class "Default")
      (node (ref "IC7") (pin "11") (pinfunction "O7_11") (pintype "passive"))
      (node (ref "L11") (pin "1") (pinfunction "1_1") (pintype "passive"))
    )
    (net (code "127") (name "Net-(IC8-OSC_OUT)") (class "Default")
      (node (ref "IC8") (pin "13") (pinfunction "OSC_OUT_13") (pintype "output"))
      (node (ref "R52") (pin "2") (pintype "passive"))
    )
    (net (code "128") (name "Net-(IC8-PA3{slash}ADC123_IN3{slash})") (class "Default")
      (node (ref "IC8") (pin "26") (pinfunction "PA3/ADC123_IN3/_26") (pintype "bidirectional"))
      (node (ref "R42") (pin "2") (pintype "passive"))
      (node (ref "R43") (pin "2") (pintype "passive"))
      (node (ref "V9") (pin "2") (pinfunction "A2_2") (pintype "passive"))
    )
    (net (code "129") (name "Net-(IC8-PB0{slash}ADC12_IN8{slash}TIM3_CH3)") (class "Default")
      (node (ref "IC8") (pin "35") (pinfunction "PB0/ADC12_IN8/TIM3_CH3_35") (pintype "bidirectional"))
      (node (ref "R44") (pin "1") (pintype "passive"))
      (node (ref "R45") (pin "1") (pintype "passive"))
      (node (ref "V10") (pin "1") (pinfunction "A1_1") (pintype "passive"))
      (node (ref "V10") (pin "2") (pinfunction "A2_2") (pintype "passive"))
    )
    (net (code "130") (name "Net-(IC8-PB1{slash}ADC12_IN9{slash}TIM3_CH4)") (class "Default")
      (node (ref "IC8") (pin "36") (pinfunction "PB1/ADC12_IN9/TIM3_CH4_36") (pintype "bidirectional"))
      (node (ref "R46") (pin "1") (pintype "passive"))
      (node (ref "R47") (pin "2") (pintype "passive"))
      (node (ref "V9") (pin "1") (pinfunction "A1_1") (pintype "passive"))
    )
    (net (code "131") (name "Net-(IC8-PC14)") (class "Default")
      (node (ref "C57") (pin "1") (pintype "passive"))
      (node (ref "G2") (pin "1") (pintype "passive"))
      (node (ref "IC8") (pin "8") (pinfunction "PC14_8") (pintype "bidirectional"))
    )
    (net (code "132") (name "Net-(IC8-PC15)") (class "Default")
      (node (ref "C58") (pin "1") (pintype "passive"))
      (node (ref "G2") (pin "2") (pintype "passive"))
      (node (ref "IC8") (pin "9") (pinfunction "PC15_9") (pintype "bidirectional"))
    )
    (net (code "133") (name "Net-(IC8-PD9)") (class "Default")
      (node (ref "IC8") (pin "56") (pinfunction "PD9_56") (pintype "bidirectional"))
      (node (ref "R36") (pin "2") (pintype "passive"))
    )
    (net (code "134") (name "Net-(IC8-PD10)") (class "Default")
      (node (ref "IC8") (pin "57") (pinfunction "PD10_57") (pintype "bidirectional"))
      (node (ref "R37") (pin "2") (pintype "passive"))
    )
    (net (code "135") (name "Net-(IC8-PD11)") (class "Default")
      (node (ref "IC8") (pin "58") (pinfunction "PD11_58") (pintype "bidirectional"))
      (node (ref "R38") (pin "2") (pintype "passive"))
    )
    (net (code "136") (name "Net-(IC8-PE0)") (class "Default")
      (node (ref "IC2") (pin "14") (pinfunction "C_14") (pintype "passive"))
      (node (ref "IC8") (pin "97") (pinfunction "PE0_97") (pintype "bidirectional"))
    )
    (net (code "137") (name "Net-(IC8-PE1)") (class "Default")
      (node (ref "IC2") (pin "16") (pinfunction "C_16") (pintype "passive"))
      (node (ref "IC8") (pin "98") (pinfunction "PE1_98") (pintype "bidirectional"))
    )
    (net (code "138") (name "Net-(IC8-PE2)") (class "Default")
      (node (ref "IC2") (pin "12") (pinfunction "C_12") (pintype "passive"))
      (node (ref "IC8") (pin "1") (pinfunction "PE2_1") (pintype "bidirectional"))
    )
    (net (code "139") (name "Net-(IC8-PE3)") (class "Default")
      (node (ref "IC2") (pin "10") (pinfunction "C_10") (pintype "passive"))
      (node (ref "IC8") (pin "2") (pinfunction "PE3_2") (pintype "bidirectional"))
    )
    (net (code "140") (name "Net-(IC8-Vbat)") (class "Default")
      (node (ref "C37") (pin "1") (pintype "passive"))
      (node (ref "IC8") (pin "6") (pinfunction "Vbat_6") (pintype "power_in"))
      (node (ref "V12") (pin "3") (pinfunction "K_3") (pintype "passive"))
    )
    (net (code "141") (name "Net-(IC8-Vcap_1)") (class "Default")
      (node (ref "C32") (pin "1") (pintype "passive"))
      (node (ref "IC8") (pin "49") (pinfunction "Vcap_1_49") (pintype "power_in"))
    )
    (net (code "142") (name "Net-(IC8-Vcap_2)") (class "Default")
      (node (ref "C33") (pin "1") (pintype "passive"))
      (node (ref "IC8") (pin "73") (pinfunction "Vcap_2_73") (pintype "power_in"))
    )
    (net (code "143") (name "Net-(IC9-IN)") (class "Default")
      (node (ref "C43") (pin "1") (pintype "passive"))
      (node (ref "IC9") (pin "1") (pinfunction "IN_1") (pintype "power_in"))
      (node (ref "L19") (pin "1") (pinfunction "1_1") (pintype "passive"))
    )
    (net (code "144") (name "Net-(IC10-C1+)") (class "Default")
      (node (ref "C5") (pin "1") (pintype "passive"))
      (node (ref "IC10") (pin "1") (pinfunction "C1+_1") (pintype "passive"))
    )
    (net (code "145") (name "Net-(IC10-C1-)") (class "Default")
      (node (ref "C5") (pin "2") (pintype "passive"))
      (node (ref "IC10") (pin "3") (pinfunction "C1-_3") (pintype "passive"))
    )
    (net (code "146") (name "Net-(IC10-C2+)") (class "Default")
      (node (ref "C6") (pin "2") (pintype "passive"))
      (node (ref "IC10") (pin "4") (pinfunction "C2+_4") (pintype "passive"))
    )
    (net (code "147") (name "Net-(IC10-C2-)") (class "Default")
      (node (ref "C6") (pin "1") (pintype "passive"))
      (node (ref "IC10") (pin "5") (pinfunction "C2-_5") (pintype "passive"))
    )
    (net (code "148") (name "Net-(IC10-VS+)") (class "Default")
      (node (ref "C7") (pin "2") (pintype "passive"))
      (node (ref "IC10") (pin "2") (pinfunction "VS+_2") (pintype "power_in"))
    )
    (net (code "149") (name "Net-(IC10-VS-)") (class "Default")
      (node (ref "C8") (pin "2") (pintype "passive"))
      (node (ref "IC10") (pin "6") (pinfunction "VS-_6") (pintype "power_in"))
    )
    (net (code "150") (name "Net-(IC11-IN)") (class "Default")
      (node (ref "C12") (pin "1") (pintype "passive"))
      (node (ref "IC11") (pin "3") (pinfunction "~{SD}_3") (pintype "passive"))
      (node (ref "IC11") (pin "5") (pinfunction "IN_5") (pintype "input"))
      (node (ref "R64") (pin "1") (pintype "passive"))
    )
    (net (code "151") (name "Net-(IC11-NR)") (class "Default")
      (node (ref "C13") (pin "2") (pintype "passive"))
      (node (ref "IC11") (pin "2") (pinfunction "NR_2") (pintype "power_in"))
    )
    (net (code "152") (name "Net-(JMP1-Pad2)") (class "Default")
      (node (ref "JMP1") (pin "2") (pintype "passive"))
      (node (ref "X20") (pin "2") (pinfunction "2_2") (pintype "passive"))
      (node (ref "X5") (pin "2") (pinfunction "2_2") (pintype "passive"))
    )
    (net (code "153") (name "Net-(L1-Pad2)") (class "Default")
      (node (ref "L1") (pin "2") (pinfunction "2_2") (pintype "passive"))
      (node (ref "X15") (pin "10") (pinfunction "10_10") (pintype "passive"))
    )
    (net (code "154") (name "Net-(L2-Pad2)") (class "Default")
      (node (ref "L2") (pin "2") (pinfunction "2_2") (pintype "passive"))
      (node (ref "X16") (pin "2") (pinfunction "2_2") (pintype "passive"))
    )
    (net (code "155") (name "Net-(L4-Pad2)") (class "Default")
      (node (ref "L4") (pin "2") (pinfunction "2_2") (pintype "passive"))
      (node (ref "X11") (pin "1") (pinfunction "1_1") (pintype "passive"))
    )
    (net (code "156") (name "Net-(L5-Pad2)") (class "Default")
      (node (ref "L5") (pin "2") (pinfunction "2_2") (pintype "passive"))
      (node (ref "X11") (pin "3") (pinfunction "3_3") (pintype "passive"))
    )
    (net (code "157") (name "Net-(L6-Pad2)") (class "Default")
      (node (ref "L6") (pin "2") (pinfunction "2_2") (pintype "passive"))
      (node (ref "X11") (pin "5") (pinfunction "5_5") (pintype "passive"))
    )
    (net (code "158") (name "Net-(L7-Pad2)") (class "Default")
      (node (ref "L7") (pin "2") (pinfunction "2_2") (pintype "passive"))
      (node (ref "X11") (pin "7") (pinfunction "7_7") (pintype "passive"))
    )
    (net (code "159") (name "Net-(L8-Pad2)") (class "Default")
      (node (ref "L8") (pin "2") (pinfunction "2_2") (pintype "passive"))
      (node (ref "X12") (pin "5") (pinfunction "5_5") (pintype "passive"))
    )
    (net (code "160") (name "Net-(L9-Pad2)") (class "Default")
      (node (ref "L9") (pin "2") (pinfunction "2_2") (pintype "passive"))
      (node (ref "X12") (pin "3") (pinfunction "3_3") (pintype "passive"))
    )
    (net (code "161") (name "Net-(L10-Pad2)") (class "Default")
      (node (ref "L10") (pin "2") (pinfunction "2_2") (pintype "passive"))
      (node (ref "X12") (pin "1") (pinfunction "1_1") (pintype "passive"))
    )
    (net (code "162") (name "Net-(L11-Pad2)") (class "Default")
      (node (ref "L11") (pin "2") (pinfunction "2_2") (pintype "passive"))
      (node (ref "X18") (pin "2") (pinfunction "2_2") (pintype "passive"))
    )
    (net (code "163") (name "Net-(L12-Pad2)") (class "Default")
      (node (ref "L12") (pin "2") (pinfunction "2_2") (pintype "passive"))
      (node (ref "X14") (pin "2") (pinfunction "2_2") (pintype "passive"))
    )
    (net (code "164") (name "Net-(L13-Pad2)") (class "Default")
      (node (ref "L13") (pin "2") (pinfunction "2_2") (pintype "passive"))
      (node (ref "X16") (pin "5") (pinfunction "5_5") (pintype "passive"))
    )
    (net (code "165") (name "Net-(L14-Pad2)") (class "Default")
      (node (ref "L14") (pin "2") (pinfunction "2_2") (pintype "passive"))
      (node (ref "X16") (pin "8") (pinfunction "8_8") (pintype "passive"))
    )
    (net (code "166") (name "Net-(L15-Pad2)") (class "Default")
      (node (ref "L15") (pin "2") (pinfunction "2_2") (pintype "passive"))
      (node (ref "X16") (pin "9") (pinfunction "9_9") (pintype "passive"))
    )
    (net (code "167") (name "Net-(L16-Pad2)") (class "Default")
      (node (ref "L16") (pin "2") (pinfunction "2_2") (pintype "passive"))
      (node (ref "X14") (pin "1") (pinfunction "1_1") (pintype "passive"))
    )
    (net (code "168") (name "Net-(L17-Pad2)") (class "Default")
      (node (ref "L17") (pin "2") (pinfunction "2_2") (pintype "passive"))
      (node (ref "X20") (pin "3") (pinfunction "3_3") (pintype "passive"))
    )
    (net (code "169") (name "Net-(L20-Pad2)") (class "Default")
      (node (ref "L20") (pin "2") (pinfunction "2_2") (pintype "passive"))
      (node (ref "X5") (pin "3") (pinfunction "3_3") (pintype "passive"))
    )
    (net (code "170") (name "Net-(L21-Pad2)") (class "Default")
      (node (ref "L21") (pin "2") (pinfunction "2_2") (pintype "passive"))
      (node (ref "X15") (pin "9") (pinfunction "9_9") (pintype "passive"))
    )
    (net (code "171") (name "Net-(L22-Pad2)") (class "Default")
      (node (ref "L22") (pin "2") (pinfunction "2_2") (pintype "passive"))
      (node (ref "X20") (pin "4") (pinfunction "4_4") (pintype "passive"))
      (node (ref "X5") (pin "4") (pinfunction "4_4") (pintype "passive"))
    )
    (net (code "172") (name "Net-(R5-Pad2)") (class "Default")
      (node (ref "R5") (pin "2") (pintype "passive"))
      (node (ref "V2") (pin "B") (pintype "passive"))
    )
    (net (code "173") (name "Net-(R7-Pad1)") (class "Default")
      (node (ref "R7") (pin "1") (pintype "passive"))
      (node (ref "V5") (pin "K") (pintype "passive"))
    )
    (net (code "174") (name "Net-(R8-Pad1)") (class "Default")
      (node (ref "R8") (pin "1") (pintype "passive"))
      (node (ref "X15") (pin "6") (pinfunction "6_6") (pintype "passive"))
    )
    (net (code "175") (name "Net-(R10-Pad1)") (class "Default")
      (node (ref "R10") (pin "1") (pintype "passive"))
      (node (ref "X15") (pin "4") (pinfunction "4_4") (pintype "passive"))
    )
    (net (code "176") (name "Net-(R11-Pad1)") (class "Default")
      (node (ref "R11") (pin "1") (pintype "passive"))
      (node (ref "X15") (pin "3") (pinfunction "3_3") (pintype "passive"))
    )
    (net (code "177") (name "Net-(R14-Pad1)") (class "Default")
      (node (ref "R14") (pin "1") (pintype "passive"))
      (node (ref "V6") (pin "B") (pinfunction "B_B") (pintype "passive"))
    )
    (net (code "178") (name "Net-(R20-Pad2)") (class "Default")
      (node (ref "R20") (pin "2") (pintype "passive"))
      (node (ref "V7") (pin "1") (pinfunction "1_1") (pintype "passive"))
      (node (ref "X9") (pin "2") (pinfunction "2_2") (pintype "passive"))
    )
    (net (code "179") (name "Net-(R21-Pad2)") (class "Default")
      (node (ref "R21") (pin "2") (pintype "passive"))
      (node (ref "V7") (pin "5") (pinfunction "5_5") (pintype "passive"))
      (node (ref "X9") (pin "3") (pinfunction "3_3") (pintype "passive"))
    )
    (net (code "180") (name "Net-(R35-Pad1)") (class "Default")
      (node (ref "R35") (pin "1") (pintype "passive"))
      (node (ref "X10") (pin "3") (pinfunction "3_3") (pintype "passive"))
    )
    (net (code "181") (name "Net-(R35-Pad2)") (class "Default")
      (node (ref "R35") (pin "2") (pintype "passive"))
      (node (ref "V8") (pin "B") (pintype "passive"))
    )
    (net (code "182") (name "Net-(V15-A2)") (class "Default")
      (node (ref "JP1") (pin "1") (pintype "passive"))
      (node (ref "L3") (pin "2") (pinfunction "2_2") (pintype "passive"))
      (node (ref "V15") (pin "2") (pinfunction "A2_2") (pintype "passive"))
    )
    (net (code "183") (name "Pgnd") (class "Default")
      (node (ref "A1") (pin "3") (pinfunction "GND_3") (pintype "passive"))
      (node (ref "A2") (pin "3") (pinfunction "GND_3") (pintype "passive"))
      (node (ref "C1") (pin "2") (pintype "passive"))
      (node (ref "C2") (pin "1") (pintype "passive"))
      (node (ref "C25") (pin "2") (pintype "passive"))
      (node (ref "C29") (pin "2") (pintype "passive"))
      (node (ref "H12") (pin "K") (pintype "passive"))
      (node (ref "IC7") (pin "9") (pinfunction "GND_9") (pintype "passive"))
      (node (ref "J1") (pin "2") (pintype "passive"))
      (node (ref "J2") (pin "1") (pintype "passive"))
      (node (ref "R1") (pin "2") (pintype "passive"))
      (node (ref "R39") (pin "1") (pintype "passive"))
      (node (ref "R40") (pin "1") (pintype "passive"))
      (node (ref "R63") (pin "2") (pintype "passive"))
      (node (ref "V1") (pin "2") (pinfunction "2_2") (pintype "passive"))
      (node (ref "V2") (pin "E") (pintype "passive"))
      (node (ref "V8") (pin "E") (pintype "passive"))
      (node (ref "X1") (pin "2") (pinfunction "2_2") (pintype "passive"))
      (node (ref "X1") (pin "4") (pinfunction "4_4") (pintype "passive"))
      (node (ref "X15") (pin "2") (pinfunction "2_2") (pintype "passive"))
      (node (ref "X2") (pin "2") (pinfunction "2_2") (pintype "passive"))
      (node (ref "X20") (pin "1") (pinfunction "1_1") (pintype "passive"))
      (node (ref "X5") (pin "1") (pinfunction "1_1") (pintype "passive"))
    )
    (net (code "184") (name "Shield") (class "Default")
      (node (ref "J1") (pin "1") (pintype "passive"))
      (node (ref "X16") (pin "10") (pinfunction "10_10") (pintype "passive"))
      (node (ref "X6") (pin "7") (pinfunction "7_7") (pintype "passive"))
      (node (ref "X7") (pin "7") (pinfunction "7_7") (pintype "passive"))
    )
    (net (code "185") (name "VCCIO") (class "Default")
      (node (ref "C23") (pin "2") (pintype "passive"))
      (node (ref "H10") (pin "A") (pinfunction "A_A") (pintype "passive"))
      (node (ref "H11") (pin "A") (pinfunction "A_A") (pintype "passive"))
      (node (ref "H9") (pin "A") (pinfunction "A_A") (pintype "passive"))
      (node (ref "IC5") (pin "17") (pinfunction "3V3OUT_17") (pintype "passive"))
      (node (ref "IC5") (pin "4") (pinfunction "VCCIO_4") (pintype "passive"))
    )
    (net (code "186") (name "Vref_3V3") (class "Default")
      (node (ref "C41") (pin "1") (pintype "passive"))
      (node (ref "C42") (pin "1") (pintype "passive"))
      (node (ref "IC8") (pin "21") (pinfunction "Vref+_21") (pintype "power_in"))
      (node (ref "IC8") (pin "22") (pinfunction "VddA_22") (pintype "power_in"))
      (node (ref "IC9") (pin "2") (pinfunction "OUT_2") (pintype "power_in"))
      (node (ref "R53") (pin "2") (pintype "passive"))
      (node (ref "R54") (pin "2") (pintype "passive"))
    )
    (net (code "187") (name "unconnected-(A2-ON{slash}OFF-Pad1)") (class "Default")
      (node (ref "A2") (pin "1") (pinfunction "ON/OFF_1") (pintype "passive"))
    )
    (net (code "188") (name "unconnected-(A2-TRIM-Pad4)") (class "Default")
      (node (ref "A2") (pin "4") (pinfunction "TRIM_4") (pintype "passive"))
    )
    (net (code "189") (name "unconnected-(B1-NC-Pad1)") (class "Default")
      (node (ref "B1") (pin "1") (pinfunction "NC_1") (pintype "passive"))
    )
    (net (code "190") (name "unconnected-(B1-NC-Pad5)") (class "Default")
      (node (ref "B1") (pin "5") (pinfunction "NC_5") (pintype "passive"))
    )
    (net (code "191") (name "unconnected-(B1-NC-Pad6)") (class "Default")
      (node (ref "B1") (pin "6") (pinfunction "NC_6") (pintype "passive"))
    )
    (net (code "192") (name "unconnected-(B1-NC-Pad7)") (class "Default")
      (node (ref "B1") (pin "7") (pinfunction "NC_7") (pintype "passive"))
    )
    (net (code "193") (name "unconnected-(B1-NC-Pad8)") (class "Default")
      (node (ref "B1") (pin "8") (pinfunction "NC_8") (pintype "passive"))
    )
    (net (code "194") (name "unconnected-(B2-NC-Pad1)") (class "Default")
      (node (ref "B2") (pin "1") (pinfunction "NC_1") (pintype "passive"))
    )
    (net (code "195") (name "unconnected-(B2-NC-Pad5)") (class "Default")
      (node (ref "B2") (pin "5") (pinfunction "NC_5") (pintype "passive"))
    )
    (net (code "196") (name "unconnected-(B2-NC-Pad6)") (class "Default")
      (node (ref "B2") (pin "6") (pinfunction "NC_6") (pintype "passive"))
    )
    (net (code "197") (name "unconnected-(B2-NC-Pad7)") (class "Default")
      (node (ref "B2") (pin "7") (pinfunction "NC_7") (pintype "passive"))
    )
    (net (code "198") (name "unconnected-(B2-NC-Pad8)") (class "Default")
      (node (ref "B2") (pin "8") (pinfunction "NC_8") (pintype "passive"))
    )
    (net (code "199") (name "unconnected-(B3-NC-Pad1)") (class "Default")
      (node (ref "B3") (pin "1") (pinfunction "NC_1") (pintype "passive"))
    )
    (net (code "200") (name "unconnected-(B3-NC-Pad5)") (class "Default")
      (node (ref "B3") (pin "5") (pinfunction "NC_5") (pintype "passive"))
    )
    (net (code "201") (name "unconnected-(B3-NC-Pad6)") (class "Default")
      (node (ref "B3") (pin "6") (pinfunction "NC_6") (pintype "passive"))
    )
    (net (code "202") (name "unconnected-(B3-NC-Pad7)") (class "Default")
      (node (ref "B3") (pin "7") (pinfunction "NC_7") (pintype "passive"))
    )
    (net (code "203") (name "unconnected-(B3-NC-Pad8)") (class "Default")
      (node (ref "B3") (pin "8") (pinfunction "NC_8") (pintype "passive"))
    )
    (net (code "204") (name "unconnected-(B4-NC-Pad1)") (class "Default")
      (node (ref "B4") (pin "1") (pinfunction "NC_1") (pintype "passive"))
    )
    (net (code "205") (name "unconnected-(B4-NC-Pad5)") (class "Default")
      (node (ref "B4") (pin "5") (pinfunction "NC_5") (pintype "passive"))
    )
    (net (code "206") (name "unconnected-(B4-NC-Pad6)") (class "Default")
      (node (ref "B4") (pin "6") (pinfunction "NC_6") (pintype "passive"))
    )
    (net (code "207") (name "unconnected-(B4-NC-Pad7)") (class "Default")
      (node (ref "B4") (pin "7") (pinfunction "NC_7") (pintype "passive"))
    )
    (net (code "208") (name "unconnected-(B4-NC-Pad8)") (class "Default")
      (node (ref "B4") (pin "8") (pinfunction "NC_8") (pintype "passive"))
    )
    (net (code "209") (name "unconnected-(IC5-NC-Pad8)") (class "Default")
      (node (ref "IC5") (pin "8") (pinfunction "NC_8") (pintype "passive"))
    )
    (net (code "210") (name "unconnected-(IC5-NC-Pad24)") (class "Default")
      (node (ref "IC5") (pin "24") (pinfunction "NC_24") (pintype "passive"))
    )
    (net (code "211") (name "unconnected-(IC5-OSCI-Pad27)") (class "Default")
      (node (ref "IC5") (pin "27") (pinfunction "OSCI_27") (pintype "passive"))
    )
    (net (code "212") (name "unconnected-(IC5-OSCO-Pad28)") (class "Default")
      (node (ref "IC5") (pin "28") (pinfunction "OSCO_28") (pintype "passive"))
    )
    (net (code "213") (name "unconnected-(IC5-~{CTS}-Pad11)") (class "Default")
      (node (ref "IC5") (pin "11") (pinfunction "~{CTS}_11") (pintype "passive"))
    )
    (net (code "214") (name "unconnected-(IC5-~{DCD}-Pad10)") (class "Default")
      (node (ref "IC5") (pin "10") (pinfunction "~{DCD}_10") (pintype "passive"))
    )
    (net (code "215") (name "unconnected-(IC5-~{DSR}-Pad9)") (class "Default")
      (node (ref "IC5") (pin "9") (pinfunction "~{DSR}_9") (pintype "passive"))
    )
    (net (code "216") (name "unconnected-(IC5-~{DTR}-Pad2)") (class "Default")
      (node (ref "IC5") (pin "2") (pinfunction "~{DTR}_2") (pintype "passive"))
    )
    (net (code "217") (name "unconnected-(IC5-~{RI}-Pad6)") (class "Default")
      (node (ref "IC5") (pin "6") (pinfunction "~{RI}_6") (pintype "passive"))
    )
    (net (code "218") (name "unconnected-(IC5-~{RTS}-Pad3)") (class "Default")
      (node (ref "IC5") (pin "3") (pinfunction "~{RTS}_3") (pintype "passive"))
    )
    (net (code "219") (name "unconnected-(IC6B-VCC-Pad8)") (class "Default")
      (node (ref "IC6") (pin "8") (pinfunction "VCC_8") (pintype "power_in"))
    )
    (net (code "220") (name "unconnected-(IC6B-VEE-Pad4)") (class "Default")
      (node (ref "IC6") (pin "4") (pinfunction "VEE_4") (pintype "power_in"))
    )
    (net (code "221") (name "unconnected-(IC8-PA5{slash}DAC_OUT2{slash}ADC12_IN5-Pad30)") (class "Default")
      (node (ref "IC8") (pin "30") (pinfunction "PA5/DAC_OUT2/ADC12_IN5_30") (pintype "bidirectional"))
    )
    (net (code "222") (name "unconnected-(IC8-PA7{slash}ADC12_IN7{slash}TIM3_CH2-Pad32)") (class "Default")
      (node (ref "IC8") (pin "32") (pinfunction "PA7/ADC12_IN7/TIM3_CH2_32") (pintype "bidirectional"))
    )
    (net (code "223") (name "unconnected-(IC8-PA8-Pad67)") (class "Default")
      (node (ref "IC8") (pin "67") (pinfunction "PA8_67") (pintype "bidirectional"))
    )
    (net (code "224") (name "unconnected-(IC8-PA11{slash}USBDM-Pad70)") (class "Default")
      (node (ref "IC8") (pin "70") (pinfunction "PA11/USBDM_70") (pintype "bidirectional"))
    )
    (net (code "225") (name "unconnected-(IC8-PA12{slash}USBDP-Pad71)") (class "Default")
      (node (ref "IC8") (pin "71") (pinfunction "PA12/USBDP_71") (pintype "bidirectional"))
    )
    (net (code "226") (name "unconnected-(IC8-PA15{slash}TIM2_CH1-Pad77)") (class "Default")
      (node (ref "IC8") (pin "77") (pinfunction "PA15/TIM2_CH1_77") (pintype "bidirectional"))
    )
    (net (code "227") (name "unconnected-(IC8-PB7{slash}{slash}I2C1_SDA-Pad93)") (class "Default")
      (node (ref "IC8") (pin "93") (pinfunction "PB7//I2C1_SDA_93") (pintype "bidirectional"))
    )
    (net (code "228") (name "unconnected-(IC8-PB9{slash}TIM11_CH1-Pad96)") (class "Default")
      (node (ref "IC8") (pin "96") (pinfunction "PB9/TIM11_CH1_96") (pintype "bidirectional"))
    )
    (net (code "229") (name "unconnected-(IC8-PB10{slash}TIM2_CH3-Pad47)") (class "Default")
      (node (ref "IC8") (pin "47") (pinfunction "PB10/TIM2_CH3_47") (pintype "bidirectional"))
    )
    (net (code "230") (name "unconnected-(IC8-PB11{slash}TIM2_CH4{slash}USART3_RX-Pad48)") (class "Default")
      (node (ref "IC8") (pin "48") (pinfunction "PB11/TIM2_CH4/USART3_RX_48") (pintype "bidirectional"))
    )
    (net (code "231") (name "unconnected-(IC8-PB12-Pad51)") (class "Default")
      (node (ref "IC8") (pin "51") (pinfunction "PB12_51") (pintype "bidirectional"))
    )
    (net (code "232") (name "unconnected-(IC8-PC12-Pad80)") (class "Default")
      (node (ref "IC8") (pin "80") (pinfunction "PC12_80") (pintype "bidirectional"))
    )
    (net (code "233") (name "unconnected-(IC8-PC13-Pad7)") (class "Default")
      (node (ref "IC8") (pin "7") (pinfunction "PC13_7") (pintype "bidirectional"))
    )
    (net (code "234") (name "unconnected-(IC8-PD8-Pad55)") (class "Default")
      (node (ref "IC8") (pin "55") (pinfunction "PD8_55") (pintype "bidirectional"))
    )
    (net (code "235") (name "unconnected-(IC8-PD14{slash}TIM4_CH3-Pad61)") (class "Default")
      (node (ref "IC8") (pin "61") (pinfunction "PD14/TIM4_CH3_61") (pintype "bidirectional"))
    )
    (net (code "236") (name "unconnected-(IC8-PD15{slash}TIM4_CH4-Pad62)") (class "Default")
      (node (ref "IC8") (pin "62") (pinfunction "PD15/TIM4_CH4_62") (pintype "bidirectional"))
    )
    (net (code "237") (name "unconnected-(IC8-PE4-Pad3)") (class "Default")
      (node (ref "IC8") (pin "3") (pinfunction "PE4_3") (pintype "bidirectional"))
    )
    (net (code "238") (name "unconnected-(IC8-PE7-Pad38)") (class "Default")
      (node (ref "IC8") (pin "38") (pinfunction "PE7_38") (pintype "bidirectional"))
    )
    (net (code "239") (name "unconnected-(IC8-PE8-Pad39)") (class "Default")
      (node (ref "IC8") (pin "39") (pinfunction "PE8_39") (pintype "bidirectional"))
    )
    (net (code "240") (name "unconnected-(IC8-PE10-Pad41)") (class "Default")
      (node (ref "IC8") (pin "41") (pinfunction "PE10_41") (pintype "bidirectional"))
    )
    (net (code "241") (name "unconnected-(IC8-PE12-Pad43)") (class "Default")
      (node (ref "IC8") (pin "43") (pinfunction "PE12_43") (pintype "bidirectional"))
    )
    (net (code "242") (name "unconnected-(IC8-PE15-Pad46)") (class "Default")
      (node (ref "IC8") (pin "46") (pinfunction "PE15_46") (pintype "bidirectional"))
    )
    (net (code "243") (name "unconnected-(IC10-DIN2-Pad10)") (class "Default")
      (node (ref "IC10") (pin "10") (pinfunction "DIN2_10") (pintype "input"))
    )
    (net (code "244") (name "unconnected-(IC10-RIN2-Pad8)") (class "Default")
      (node (ref "IC10") (pin "8") (pinfunction "RIN2_8") (pintype "input"))
    )
    (net (code "245") (name "unconnected-(IC10-~{DOUT2}-Pad7)") (class "Default")
      (node (ref "IC10") (pin "7") (pinfunction "~{DOUT2}_7") (pintype "output"))
    )
    (net (code "246") (name "unconnected-(IC10-~{ROUT2}-Pad9)") (class "Default")
      (node (ref "IC10") (pin "9") (pinfunction "~{ROUT2}_9") (pintype "output"))
    )
    (net (code "247") (name "unconnected-(IC11-~{ERR}-Pad6)") (class "Default")
      (node (ref "IC11") (pin "6") (pinfunction "~{ERR}_6") (pintype "power_in"))
    )
    (net (code "248") (name "unconnected-(V1-Pad3)") (class "Default")
      (node (ref "V1") (pin "3") (pinfunction "3_3") (pintype "passive"))
    )
    (net (code "249") (name "unconnected-(V4-Pad3)") (class "Default")
      (node (ref "V4") (pin "3") (pinfunction "3_3") (pintype "passive"))
    )
    (net (code "250") (name "unconnected-(V7-Pad3)") (class "Default")
      (node (ref "V7") (pin "3") (pinfunction "3_3") (pintype "passive"))
    )
    (net (code "251") (name "unconnected-(X8-Pad2)") (class "Default")
      (node (ref "X8") (pin "2") (pinfunction "2_2") (pintype "passive"))
    )
    (net (code "252") (name "unconnected-(X9-Pad4)") (class "Default")
      (node (ref "X9") (pin "4") (pinfunction "4_4") (pintype "passive"))
    )
    (net (code "253") (name "unconnected-(X10-Pad2)") (class "Default")
      (node (ref "X10") (pin "2") (pinfunction "2_2") (pintype "passive"))
    )
  )
)
